# IoTa_1_0.net
KiCad netlist of a schematic drawn in Altium Designer
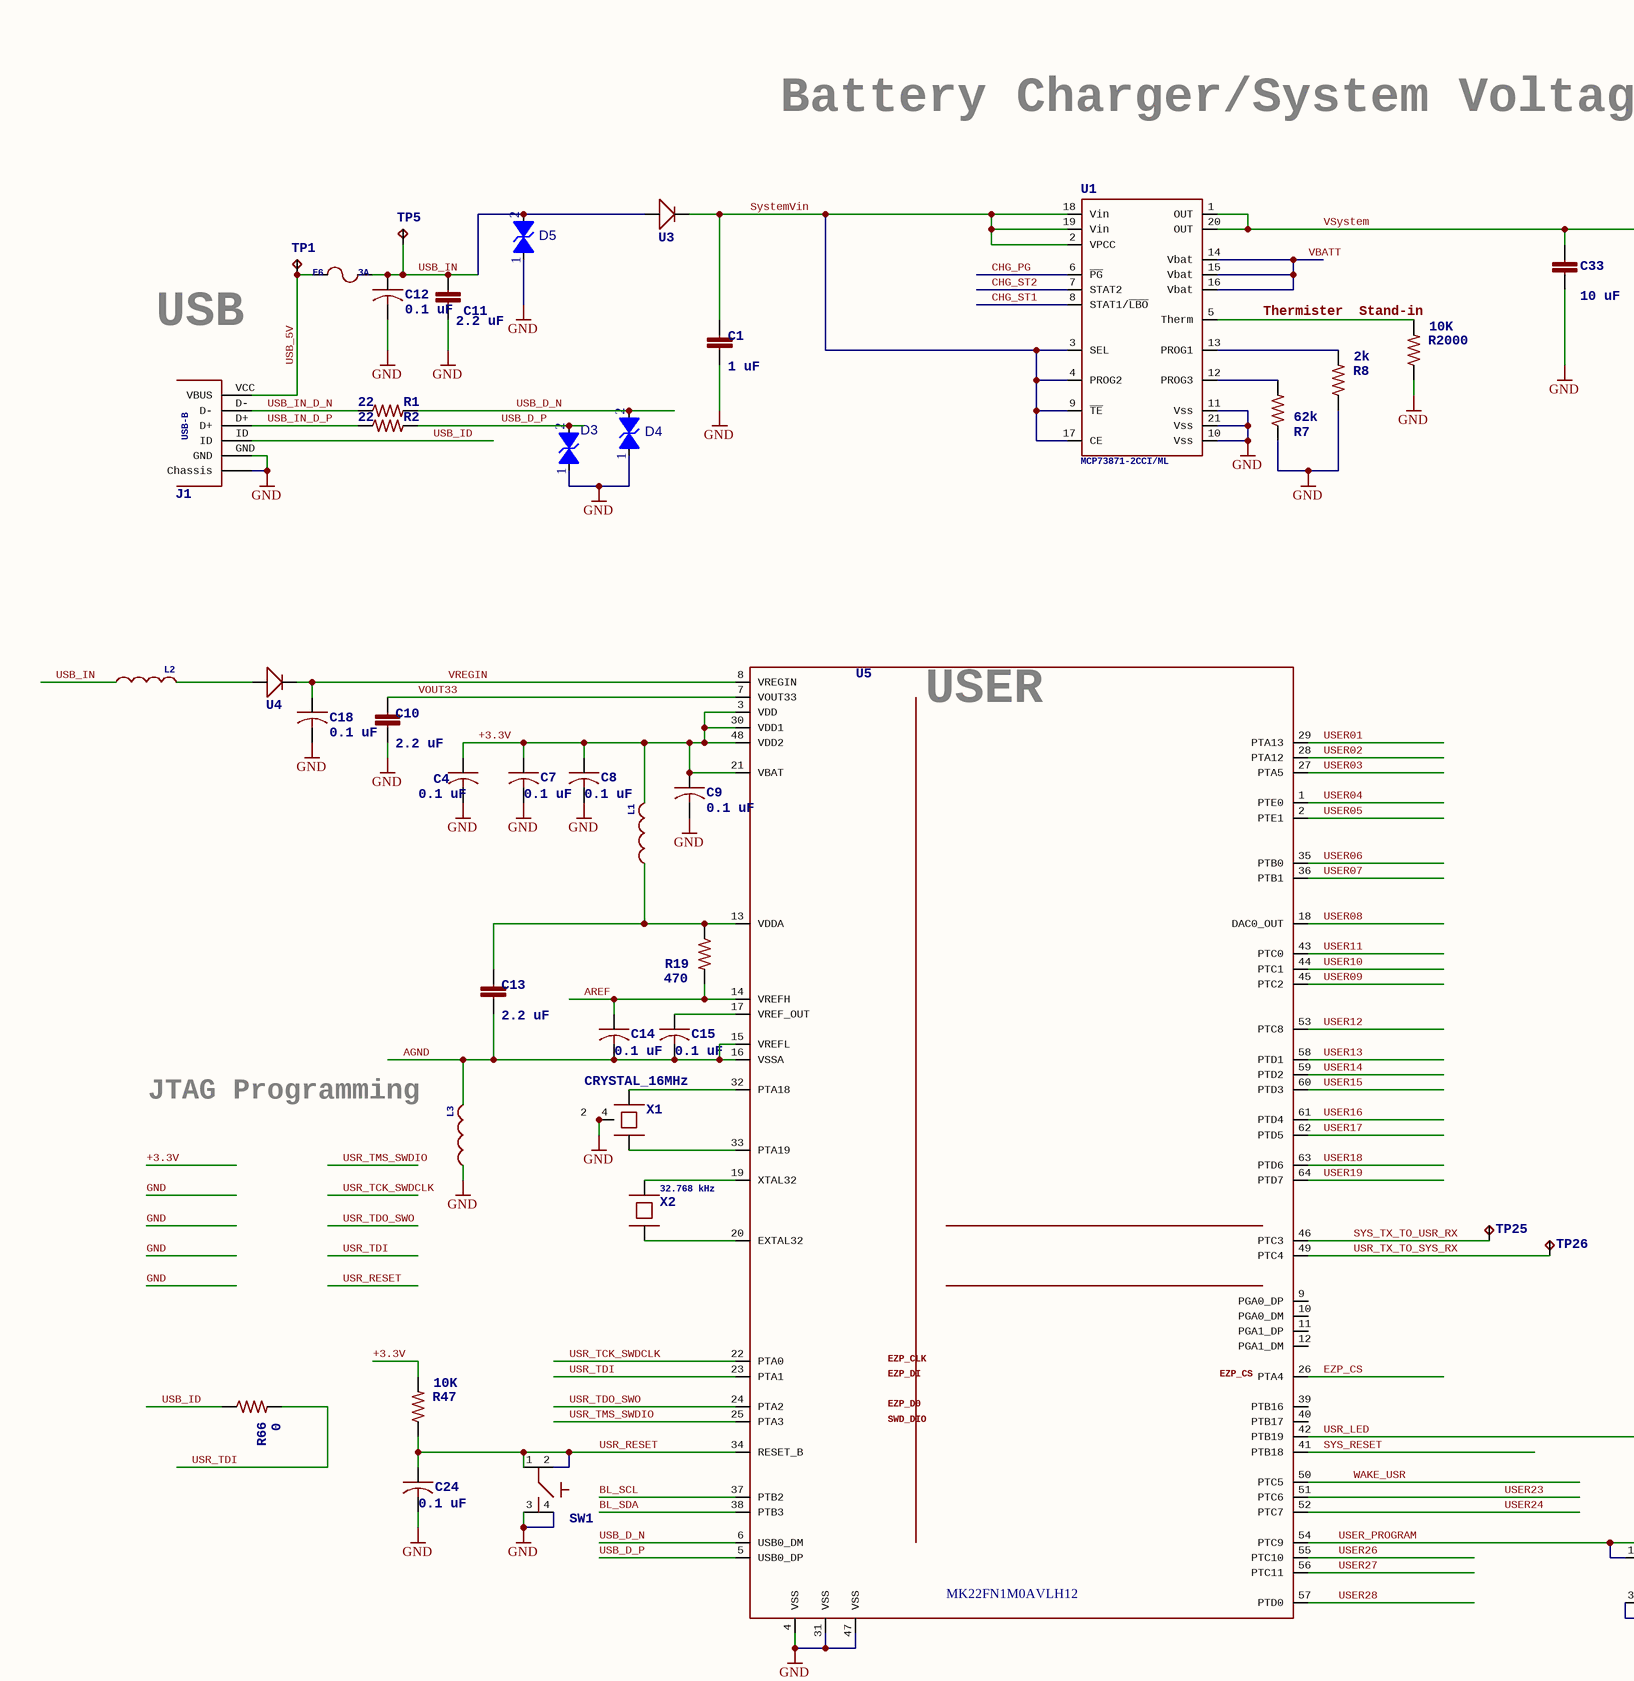
[diagram p0: IoTa_1_0.SchDoc, top left]
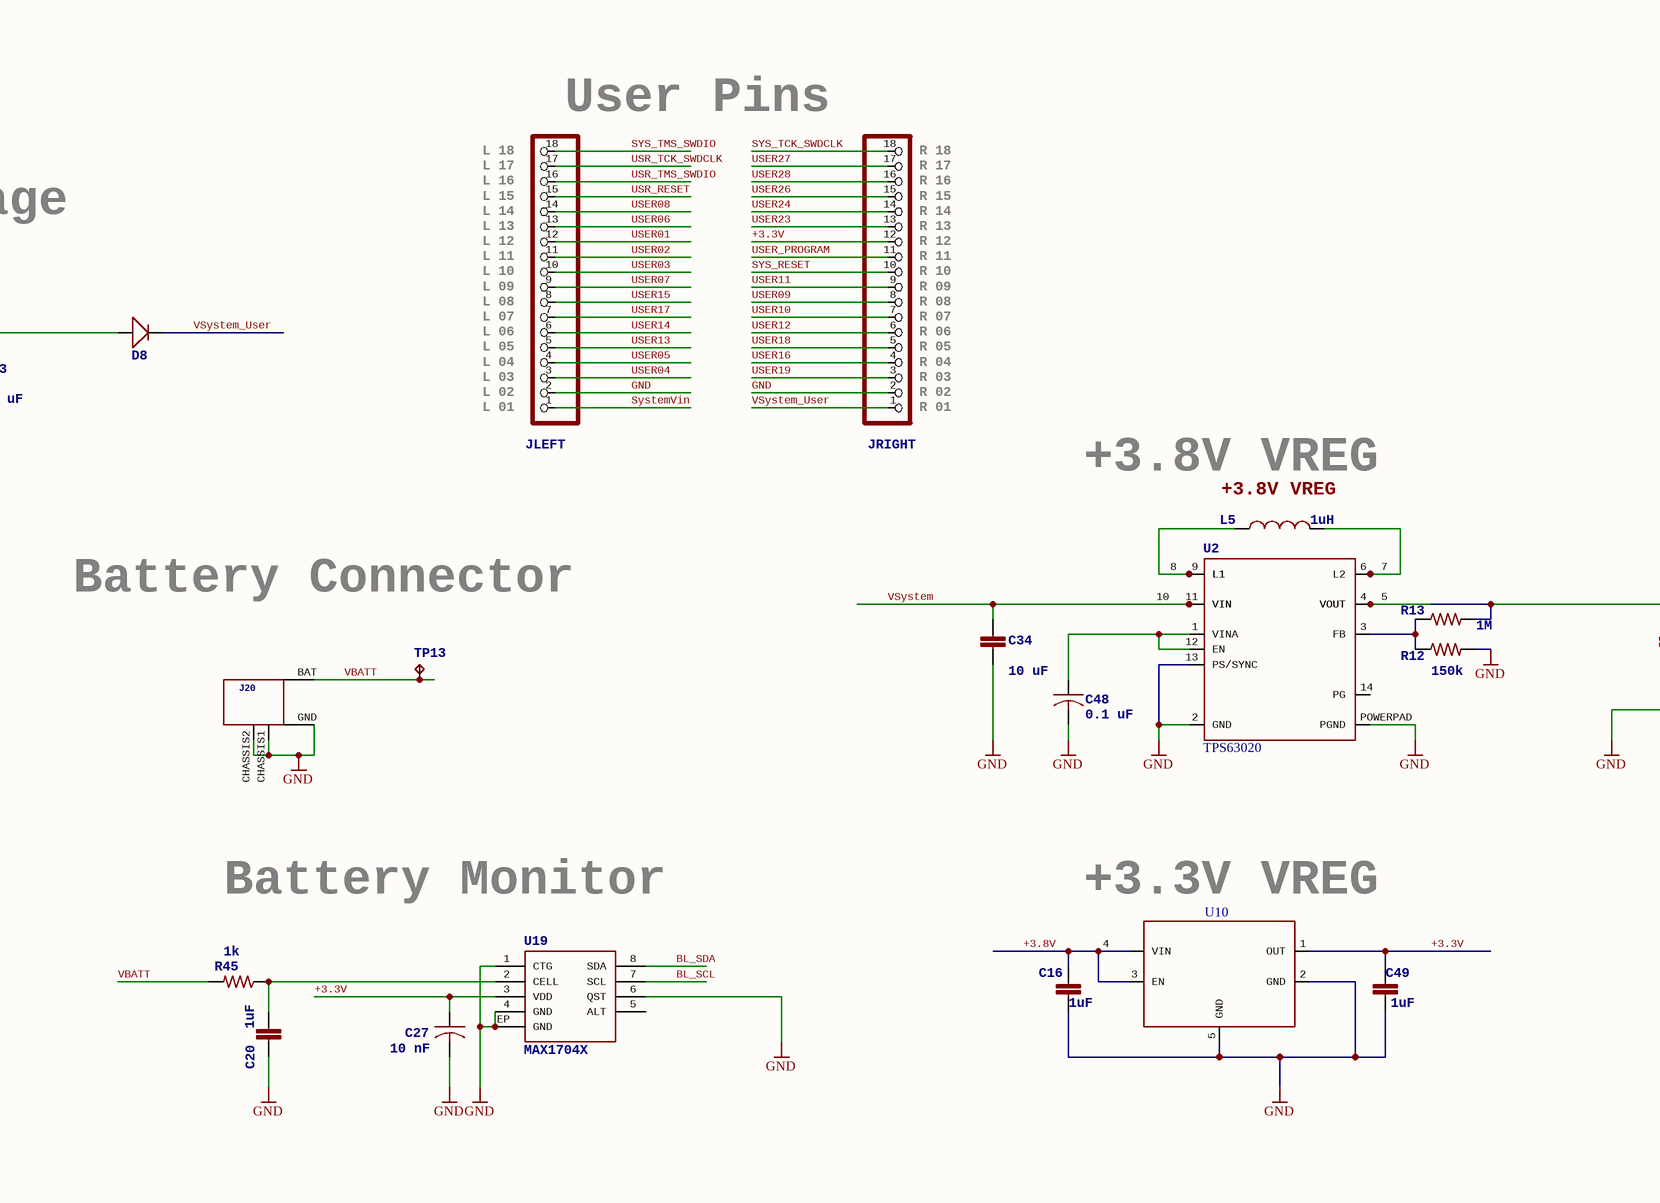
[diagram p1: IoTa_1_0.SchDoc, top middle]
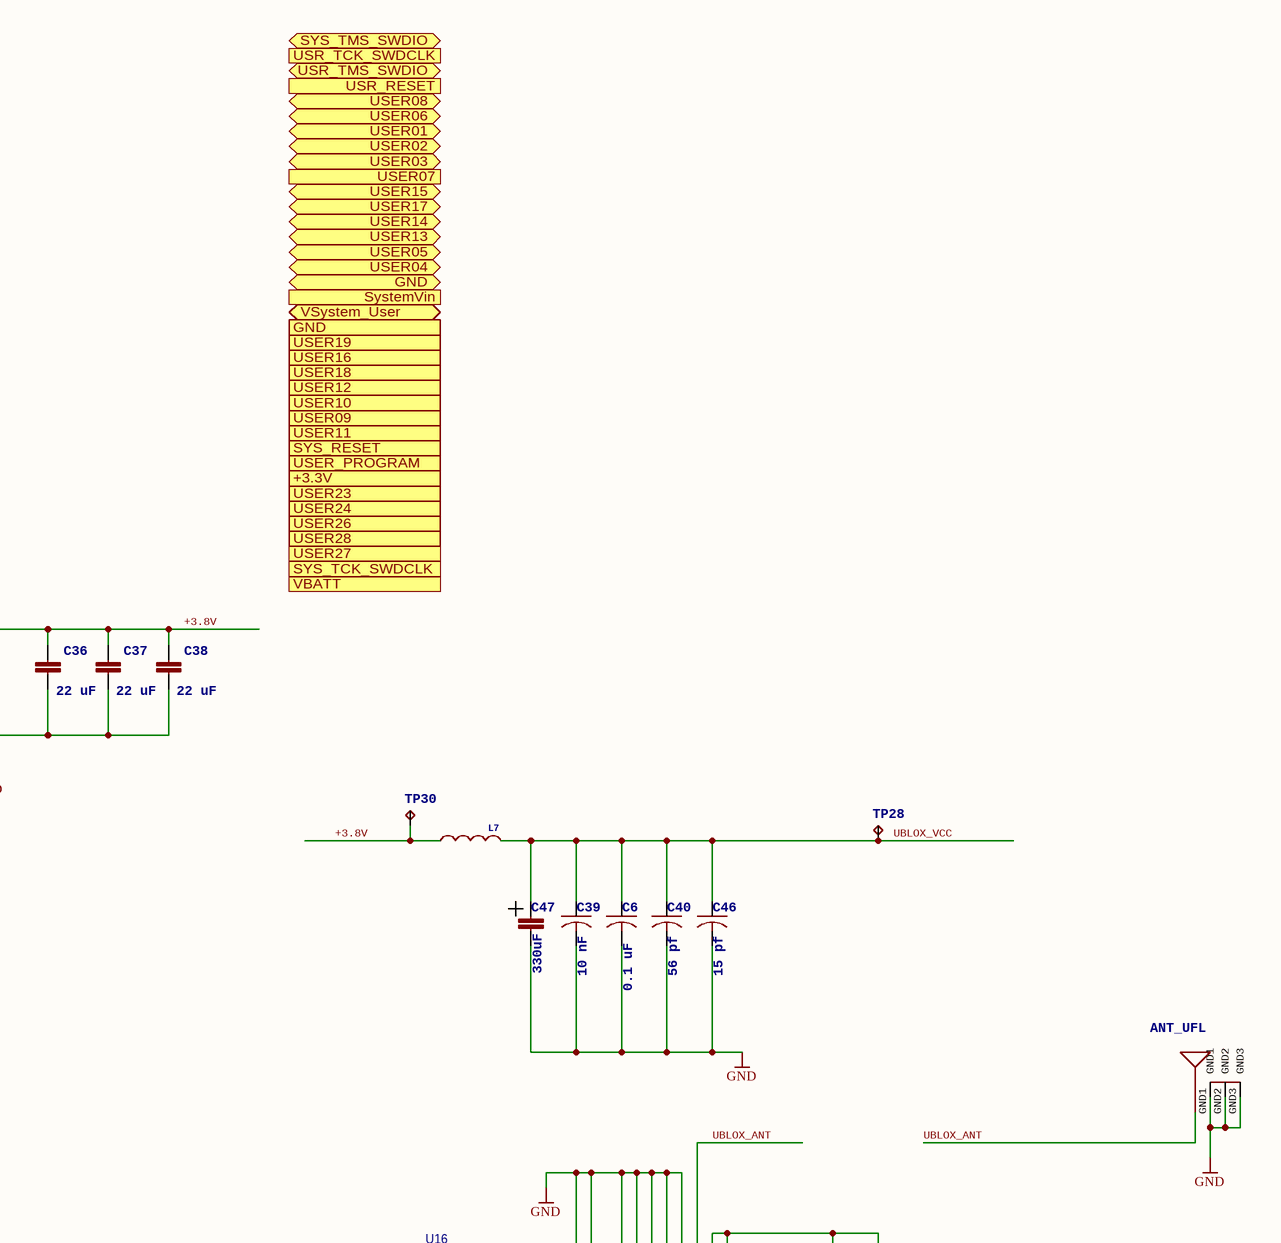
[diagram p2: IoTa_1_0.SchDoc, top right]
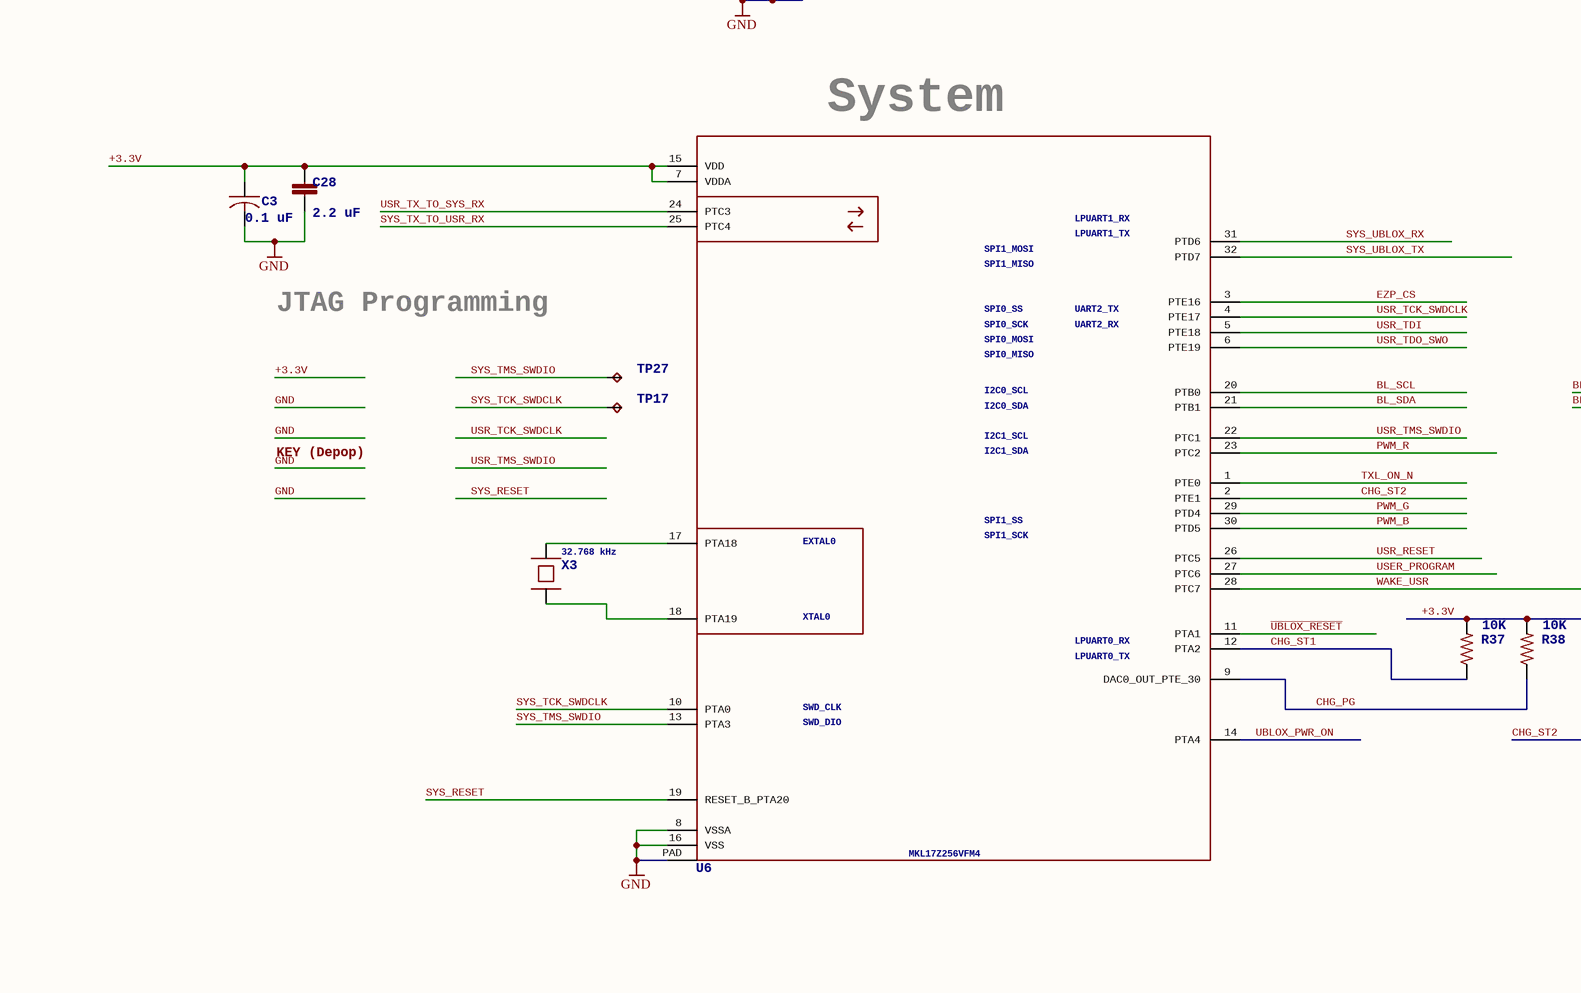
[diagram p3: IoTa_1_0.SchDoc, bottom left]
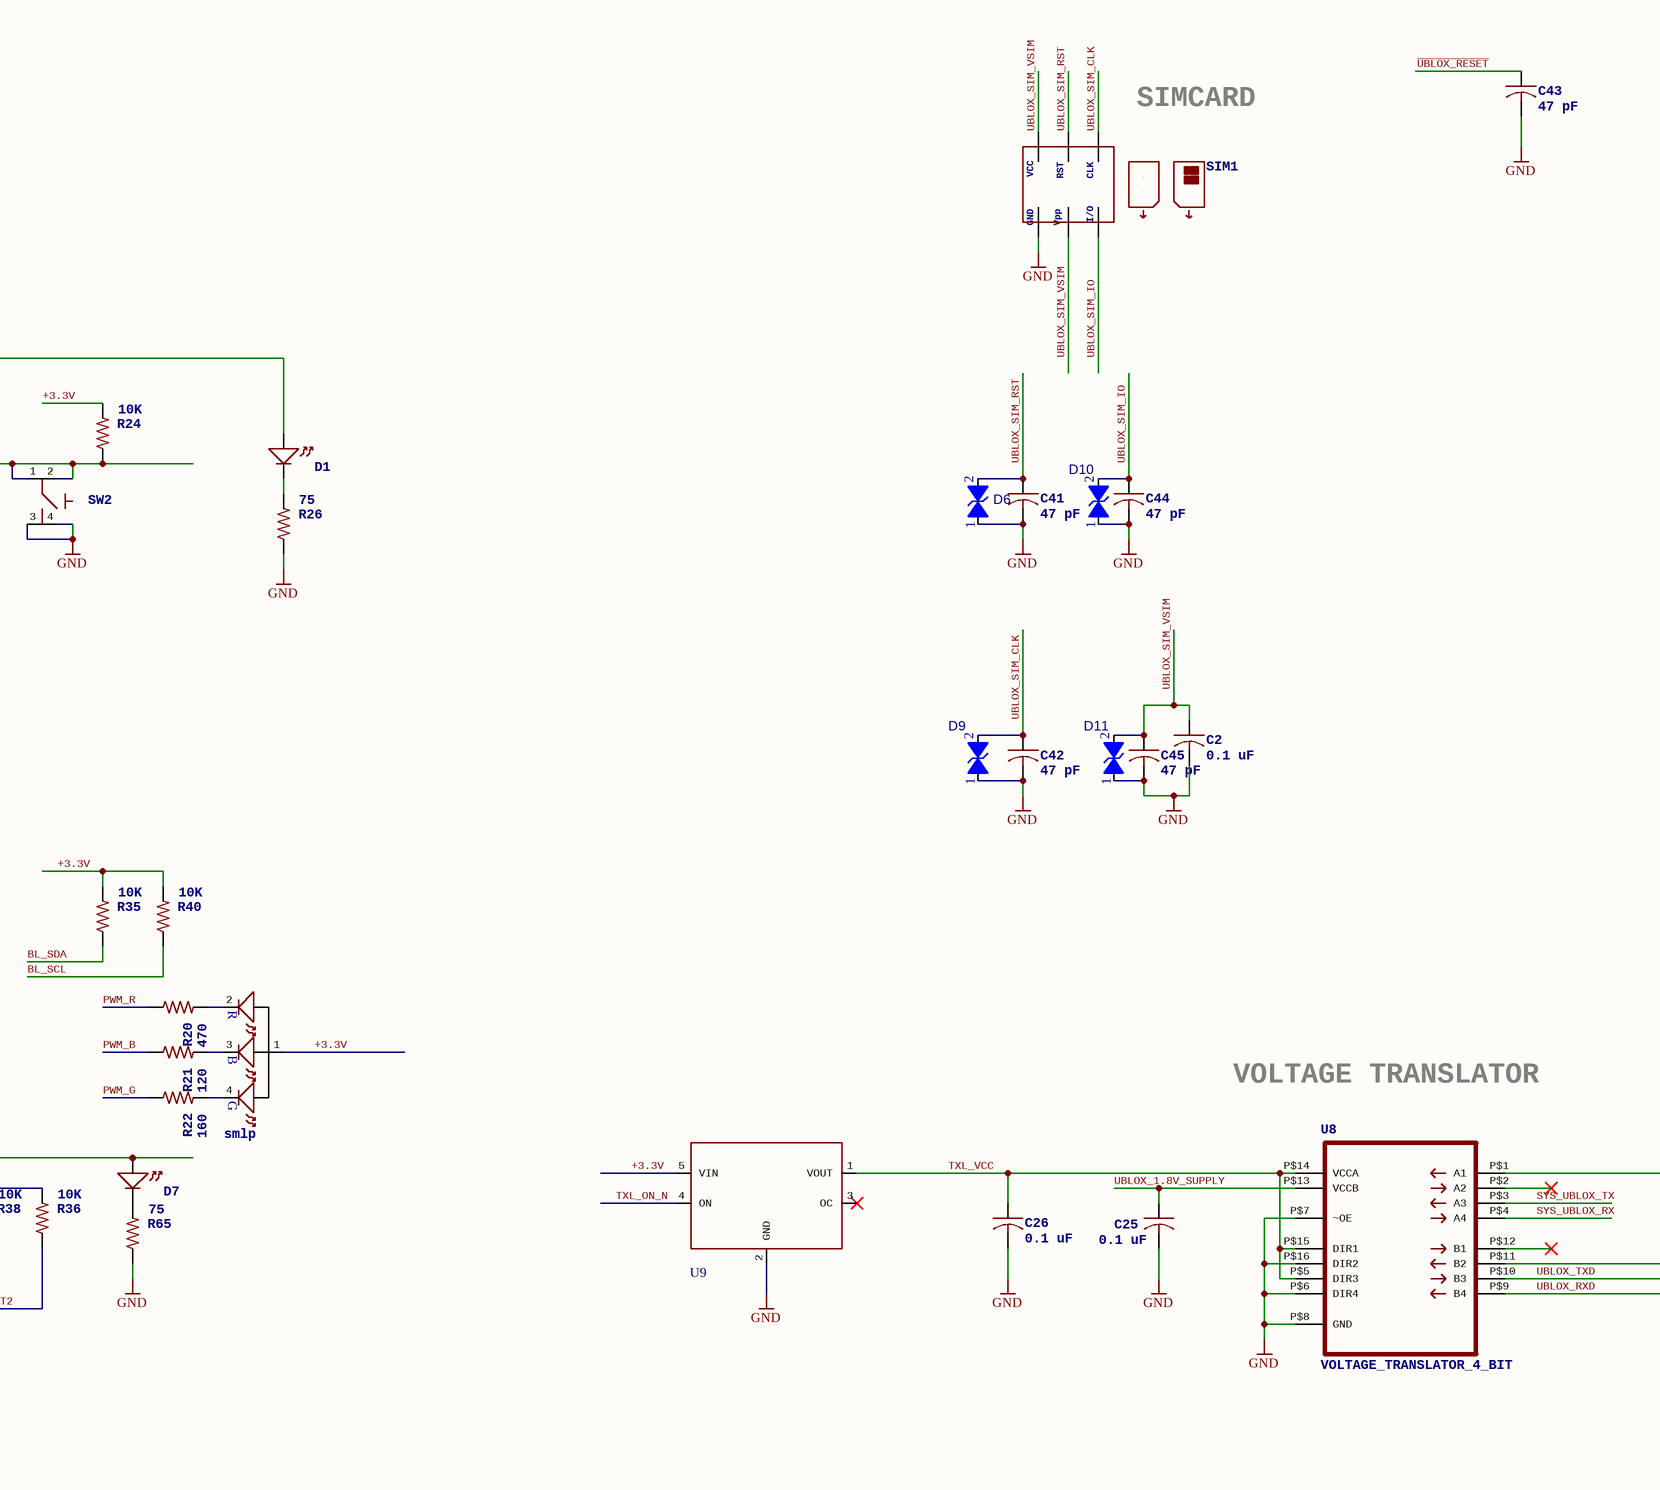
[diagram p4: IoTa_1_0.SchDoc, bottom middle]
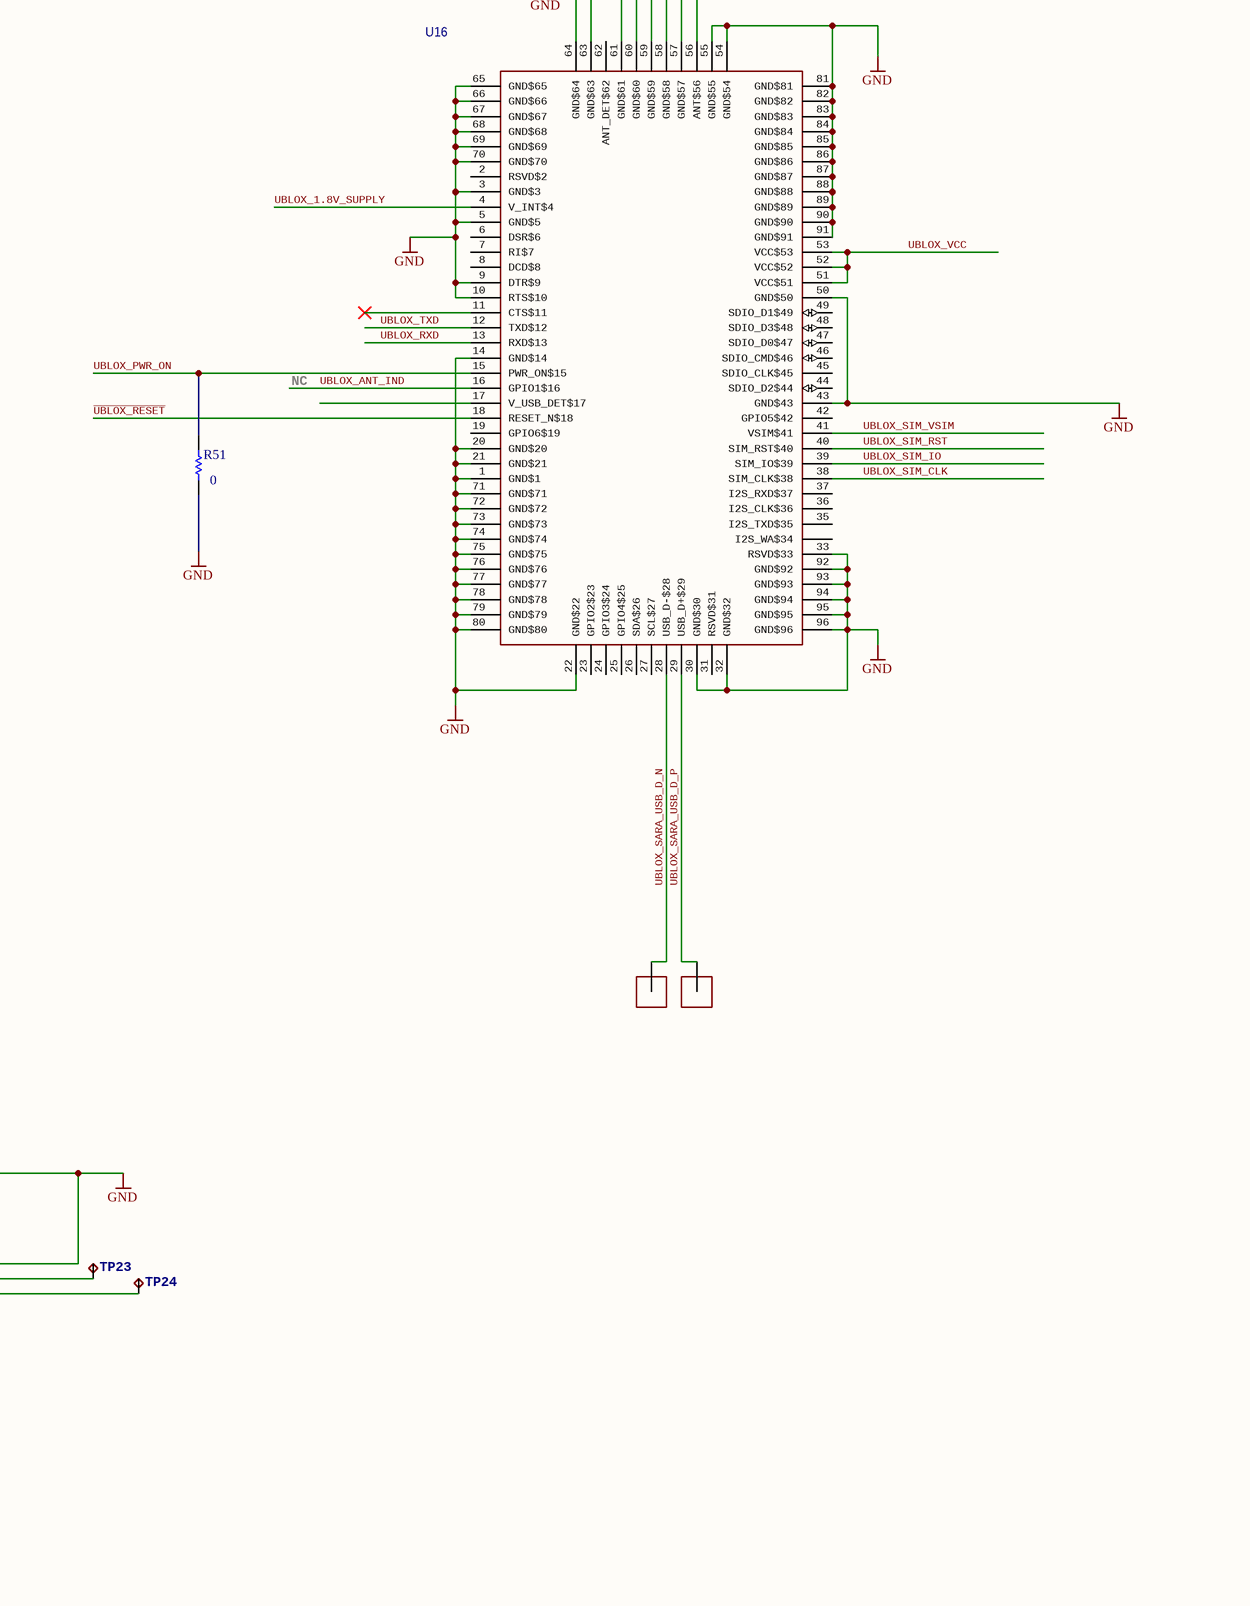
[diagram p5: IoTa_1_0.SchDoc, bottom right]

(export (version "E")
  (design (tool "Eeschema 10.0.6"))
  (components
    (comp (ref "ANT_UFL")
      (value "ANT-A-1JB")
      (footprint "UFL")
      (description "Amphenol")
      (fields (field (name "MPN") "A-1JB"))
      (libsource (lib "KON-SU260") (part "ANT-A-1JB"))
    )
    (comp (ref "C1")
      (value "1 uF")
      (footprint "KON-SU260:CAP0603")
      (description "Capacitor, 1 uF, 0603")
      (fields (field (name "MPN") "GRM188R71C105KA12D") (field (name "MFG") "MURATA"))
      (libsource (lib "KON-SU260") (part "CAP1uF_0603"))
    )
    (comp (ref "C2")
      (value "0.1 uF")
      (footprint "KON-SU260:CAP0402")
      (description "CAPACITOR, 0.1 uF, 0402")
      (fields (field (name "MFG") "MURATA") (field (name "MPN") "GRM155R61C104KA88D"))
      (libsource (lib "KON-SU260") (part "CAP0.1uF_0402"))
    )
    (comp (ref "C3")
      (value "0.1 uF")
      (footprint "KON-SU260:CAP0402")
      (description "CAPACITOR, 0.1 uF, 0402")
      (fields (field (name "MFG") "MURATA") (field (name "MPN") "GRM155R61C104KA88D"))
      (libsource (lib "KON-SU260") (part "CAP0.1uF_0402"))
    )
    (comp (ref "C4")
      (value "0.1 uF")
      (footprint "KON-SU260:CAP0402")
      (description "CAPACITOR, 0.1 uF, 0402")
      (fields (field (name "MFG") "MURATA") (field (name "MPN") "GRM155R61C104KA88D"))
      (libsource (lib "KON-SU260") (part "CAP0.1uF_0402"))
    )
    (comp (ref "C6")
      (value "0.1 uF")
      (footprint "KON-SU260:CAP0402")
      (description "CAPACITOR, 0.1 uF, 0402")
      (fields (field (name "MFG") "MURATA") (field (name "MPN") "GRM155R61C104KA88D"))
      (libsource (lib "KON-SU260") (part "CAP0.1uF_0402"))
    )
    (comp (ref "C7")
      (value "0.1 uF")
      (footprint "KON-SU260:CAP0402")
      (description "CAPACITOR, 0.1 uF, 0402")
      (fields (field (name "MFG") "MURATA") (field (name "MPN") "GRM155R61C104KA88D"))
      (libsource (lib "KON-SU260") (part "CAP0.1uF_0402"))
    )
    (comp (ref "C8")
      (value "0.1 uF")
      (footprint "KON-SU260:CAP0402")
      (description "CAPACITOR, 0.1 uF, 0402")
      (fields (field (name "MFG") "MURATA") (field (name "MPN") "GRM155R61C104KA88D"))
      (libsource (lib "KON-SU260") (part "CAP0.1uF_0402"))
    )
    (comp (ref "C9")
      (value "0.1 uF")
      (footprint "KON-SU260:CAP0402")
      (description "CAPACITOR, 0.1 uF, 0402")
      (fields (field (name "MFG") "MURATA") (field (name "MPN") "GRM155R61C104KA88D"))
      (libsource (lib "KON-SU260") (part "CAP0.1uF_0402"))
    )
    (comp (ref "C10")
      (value "2.2 uF")
      (footprint "KON-SU260:CAP0603")
      (description "Capacitor, 2.2 uF, 0603")
      (fields (field (name "MPN") "CL10A225MQ8NNNC") (field (name "MFG") "SAMSUNG"))
      (libsource (lib "KON-SU260") (part "CAP2.2uF_0603"))
    )
    (comp (ref "C11")
      (value "2.2 uF")
      (footprint "KON-SU260:CAP0603")
      (description "Capacitor, 2.2 uF, 0603")
      (fields (field (name "MPN") "CL10A225MQ8NNNC") (field (name "MFG") "SAMSUNG"))
      (libsource (lib "KON-SU260") (part "CAP2.2uF_0603"))
    )
    (comp (ref "C12")
      (value "0.1 uF")
      (footprint "KON-SU260:CAP0402")
      (description "CAPACITOR, 0.1 uF, 0402")
      (fields (field (name "MFG") "MURATA") (field (name "MPN") "GRM155R61C104KA88D"))
      (libsource (lib "KON-SU260") (part "CAP0.1uF_0402"))
    )
    (comp (ref "C13")
      (value "2.2 uF")
      (footprint "KON-SU260:CAP0603")
      (description "Capacitor, 2.2 uF, 0603")
      (fields (field (name "MPN") "CL10A225MQ8NNNC") (field (name "MFG") "SAMSUNG"))
      (libsource (lib "KON-SU260") (part "CAP2.2uF_0603"))
    )
    (comp (ref "C14")
      (value "0.1 uF")
      (footprint "KON-SU260:CAP0402")
      (description "CAPACITOR, 0.1 uF, 0402")
      (fields (field (name "MFG") "MURATA") (field (name "MPN") "GRM155R61C104KA88D"))
      (libsource (lib "KON-SU260") (part "CAP0.1uF_0402"))
    )
    (comp (ref "C15")
      (value "0.1 uF")
      (footprint "KON-SU260:CAP0402")
      (description "CAPACITOR, 0.1 uF, 0402")
      (fields (field (name "MFG") "MURATA") (field (name "MPN") "GRM155R61C104KA88D"))
      (libsource (lib "KON-SU260") (part "CAP0.1uF_0402"))
    )
    (comp (ref "C16")
      (value "1uF")
      (footprint "KON-SU260:CAP0402")
      (description "CAPACITOR, 1uF, 0402")
      (fields (field (name "MPN") "04026D105KAT2A") (field (name "MFG") "AVX"))
      (libsource (lib "KON-SU260") (part "CAP1uF_0402"))
    )
    (comp (ref "C18")
      (value "0.1 uF")
      (footprint "KON-SU260:CAP0402")
      (description "CAPACITOR, 0.1 uF, 0402")
      (fields (field (name "MFG") "MURATA") (field (name "MPN") "GRM155R61C104KA88D"))
      (libsource (lib "KON-SU260") (part "CAP0.1uF_0402"))
    )
    (comp (ref "C20")
      (value "1uF")
      (footprint "KON-SU260:CAP0402")
      (description "CAPACITOR, 1uF, 0402")
      (fields (field (name "MPN") "04026D105KAT2A") (field (name "MFG") "AVX"))
      (libsource (lib "KON-SU260") (part "CAP1uF_0402"))
    )
    (comp (ref "C24")
      (value "0.1 uF")
      (footprint "KON-SU260:CAP0402")
      (description "CAPACITOR, 0.1 uF, 0402")
      (fields (field (name "MFG") "MURATA") (field (name "MPN") "GRM155R61C104KA88D"))
      (libsource (lib "KON-SU260") (part "CAP0.1uF_0402"))
    )
    (comp (ref "C25")
      (value "0.1 uF")
      (footprint "KON-SU260:CAP0402")
      (description "CAPACITOR, 0.1 uF, 0402")
      (fields (field (name "MFG") "MURATA") (field (name "MPN") "GRM155R61C104KA88D"))
      (libsource (lib "KON-SU260") (part "CAP0.1uF_0402"))
    )
    (comp (ref "C26")
      (value "0.1 uF")
      (footprint "KON-SU260:CAP0402")
      (description "CAPACITOR, 0.1 uF, 0402")
      (fields (field (name "MFG") "MURATA") (field (name "MPN") "GRM155R61C104KA88D"))
      (libsource (lib "KON-SU260") (part "CAP0.1uF_0402"))
    )
    (comp (ref "C27")
      (value "10 nF")
      (footprint "KON-SU260:CAP0402")
      (description "CAPACITOR, 10 nF, 0402")
      (fields (field (name "MFG") "MURATA") (field (name "MPN") "GRM155R71C103KA01D"))
      (libsource (lib "KON-SU260") (part "CAP10nF_0402"))
    )
    (comp (ref "C28")
      (value "2.2 uF")
      (footprint "KON-SU260:CAP0603")
      (description "Capacitor, 2.2 uF, 0603")
      (fields (field (name "MPN") "CL10A225MQ8NNNC") (field (name "MFG") "SAMSUNG"))
      (libsource (lib "KON-SU260") (part "CAP2.2uF_0603"))
    )
    (comp (ref "C33")
      (value "10 uF")
      (footprint "KON-SU260:CAP0603")
      (description "Capacitor, 10 uF, 0603")
      (fields (field (name "MPN") "GRM188R60J106ME84D") (field (name "MFG") "Murata"))
      (libsource (lib "KON-SU260") (part "CAP10uF_0603"))
    )
    (comp (ref "C34")
      (value "10 uF")
      (footprint "KON-SU260:CAP0603")
      (description "Capacitor, 10 uF, 0603")
      (fields (field (name "MPN") "GRM188R60J106ME84D") (field (name "MFG") "Murata"))
      (libsource (lib "KON-SU260") (part "CAP10uF_0603"))
    )
    (comp (ref "C36")
      (value "22 uF")
      (footprint "KON-SU260:CAP0603")
      (description "Capacitor, 22 uF, 0603")
      (fields (field (name "MPN") "GRM188R60J226MEA0D") (field (name "MFG") "MURATA"))
      (libsource (lib "KON-SU260") (part "CAP22uF_0603"))
    )
    (comp (ref "C37")
      (value "22 uF")
      (footprint "KON-SU260:CAP0603")
      (description "Capacitor, 22 uF, 0603")
      (fields (field (name "MPN") "GRM188R60J226MEA0D") (field (name "MFG") "MURATA"))
      (libsource (lib "KON-SU260") (part "CAP22uF_0603"))
    )
    (comp (ref "C38")
      (value "22 uF")
      (footprint "KON-SU260:CAP0603")
      (description "Capacitor, 22 uF, 0603")
      (fields (field (name "MPN") "GRM188R60J226MEA0D") (field (name "MFG") "MURATA"))
      (libsource (lib "KON-SU260") (part "CAP22uF_0603"))
    )
    (comp (ref "C39")
      (value "10 nF")
      (footprint "KON-SU260:CAP0402")
      (description "CAPACITOR, 10 nF, 0402")
      (fields (field (name "MFG") "MURATA") (field (name "MPN") "GRM155R71C103KA01D"))
      (libsource (lib "KON-SU260") (part "CAP10nF_0402"))
    )
    (comp (ref "C40")
      (value "56 pf")
      (footprint "KON-SU260:CAP0402")
      (description "CAPACITOR, 56 pF, 0402")
      (fields (field (name "MFG") "KEMET") (field (name "MPN") "C0402C560J5GACTU"))
      (libsource (lib "KON-SU260") (part "CAP56pF_0402"))
    )
    (comp (ref "C41")
      (value "47 pF")
      (footprint "KON-SU260:CAP0402")
      (description "CAPACITOR, 47 pF, 0402")
      (fields (field (name "MFG") "AVX") (field (name "MPN") "04025A470JAT2A"))
      (libsource (lib "KON-SU260") (part "CAP47pf_0402"))
    )
    (comp (ref "C42")
      (value "47 pF")
      (footprint "KON-SU260:CAP0402")
      (description "CAPACITOR, 47 pF, 0402")
      (fields (field (name "MFG") "AVX") (field (name "MPN") "04025A470JAT2A"))
      (libsource (lib "KON-SU260") (part "CAP47pf_0402"))
    )
    (comp (ref "C43")
      (value "47 pF")
      (footprint "KON-SU260:CAP0402")
      (description "CAPACITOR, 47 pF, 0402")
      (fields (field (name "MFG") "AVX") (field (name "MPN") "04025A470JAT2A"))
      (libsource (lib "KON-SU260") (part "CAP47pf_0402"))
    )
    (comp (ref "C44")
      (value "47 pF")
      (footprint "KON-SU260:CAP0402")
      (description "CAPACITOR, 47 pF, 0402")
      (fields (field (name "MFG") "AVX") (field (name "MPN") "04025A470JAT2A"))
      (libsource (lib "KON-SU260") (part "CAP47pf_0402"))
    )
    (comp (ref "C45")
      (value "47 pF")
      (footprint "KON-SU260:CAP0402")
      (description "CAPACITOR, 47 pF, 0402")
      (fields (field (name "MFG") "AVX") (field (name "MPN") "04025A470JAT2A"))
      (libsource (lib "KON-SU260") (part "CAP47pf_0402"))
    )
    (comp (ref "C46")
      (value "15 pf")
      (footprint "KON-SU260:CAP0402")
      (description "CAPACITOR, 15 pF, 0402")
      (fields (field (name "MFG") "AVX/ELCO") (field (name "MPN") "04025A150JAT2A"))
      (libsource (lib "KON-SU260") (part "CAP15pF_0402"))
    )
    (comp (ref "C47")
      (value "330uF")
      (footprint "KON-SU260:CAP1210POL")
      (description "Capacitor, 330 uF, 1210, Polarized Tantalum")
      (fields (field (name "MPN") "F950J337MBAAQ2") (field (name "MFG") "AVX"))
      (libsource (lib "KON-SU260") (part "CAP330uF_1210P"))
    )
    (comp (ref "C48")
      (value "0.1 uF")
      (footprint "KON-SU260:CAP0402")
      (description "CAPACITOR, 0.1 uF, 0402")
      (fields (field (name "MFG") "MURATA") (field (name "MPN") "GRM155R61C104KA88D"))
      (libsource (lib "KON-SU260") (part "CAP0.1uF_0402"))
    )
    (comp (ref "C49")
      (value "1uF")
      (footprint "KON-SU260:CAP0402")
      (description "CAPACITOR, 1uF, 0402")
      (fields (field (name "MPN") "04026D105KAT2A") (field (name "MFG") "AVX"))
      (libsource (lib "KON-SU260") (part "CAP1uF_0402"))
    )
    (comp (ref "D1")
      (value "LED_0402_VLMW")
      (footprint "LED_0402_VISHAY_VLMW")
      (description "LED, Vishay White 0402")
      (fields (field (name "MFG") "VISHAY") (field (name "MPN") "VLMW1500-GS08"))
      (libsource (lib "KON-SU260") (part "LED_0402_VLMW"))
    )
    (comp (ref "D3")
      (value "~")
      (footprint "PESD_0402")
      (description "DIODE,ZENER VOLTAGE SUPPRESSOR,+/-14V")
      (fields (field (name "MFG") "Littlefuse") (field (name "MPN") "PESD0402-140"))
      (libsource (lib "KON-SU260") (part "PESD_14V"))
    )
    (comp (ref "D4")
      (value "~")
      (footprint "PESD_0402")
      (description "DIODE,ZENER VOLTAGE SUPPRESSOR,+/-14V")
      (fields (field (name "MFG") "Littlefuse") (field (name "MPN") "PESD0402-140"))
      (libsource (lib "KON-SU260") (part "PESD_14V"))
    )
    (comp (ref "D5")
      (value "~")
      (footprint "PESD_0402")
      (description "DIODE,ZENER VOLTAGE SUPPRESSOR,+/-14V")
      (fields (field (name "MFG") "Littlefuse") (field (name "MPN") "PESD0402-140"))
      (libsource (lib "KON-SU260") (part "PESD_14V"))
    )
    (comp (ref "D6")
      (value "~")
      (footprint "PESD_0402")
      (description "DIODE,ZENER VOLTAGE SUPPRESSOR,+/-14V")
      (fields (field (name "MFG") "Littlefuse") (field (name "MPN") "PESD0402-140"))
      (libsource (lib "KON-SU260") (part "PESD_14V"))
    )
    (comp (ref "D7")
      (value "LED_0402_VLMW")
      (footprint "LED_0402_VISHAY_VLMW")
      (description "LED, Vishay White 0402")
      (fields (field (name "MFG") "VISHAY") (field (name "MPN") "VLMW1500-GS08"))
      (libsource (lib "KON-SU260") (part "LED_0402_VLMW"))
    )
    (comp (ref "D8")
      (value "CDBQR0230L")
      (footprint "DIODE_0402")
      (description "Schottky Barrier Diode, 200 mA, 30 V, 0402 package")
      (fields (field (name "MFG") "Comchip"))
      (libsource (lib "KON-SU260") (part "DIODE_0402_200mA"))
    )
    (comp (ref "D9")
      (value "~")
      (footprint "PESD_0402")
      (description "DIODE,ZENER VOLTAGE SUPPRESSOR,+/-14V")
      (fields (field (name "MFG") "Littlefuse") (field (name "MPN") "PESD0402-140"))
      (libsource (lib "KON-SU260") (part "PESD_14V"))
    )
    (comp (ref "D10")
      (value "~")
      (footprint "PESD_0402")
      (description "DIODE,ZENER VOLTAGE SUPPRESSOR,+/-14V")
      (fields (field (name "MFG") "Littlefuse") (field (name "MPN") "PESD0402-140"))
      (libsource (lib "KON-SU260") (part "PESD_14V"))
    )
    (comp (ref "D11")
      (value "~")
      (footprint "PESD_0402")
      (description "DIODE,ZENER VOLTAGE SUPPRESSOR,+/-14V")
      (fields (field (name "MFG") "Littlefuse") (field (name "MPN") "PESD0402-140"))
      (libsource (lib "KON-SU260") (part "PESD_14V"))
    )
    (comp (ref "F6")
      (value "3A")
      (footprint "KON-SU260:RES0603")
      (description "Fuse, 3A, 0603")
      (fields (field (name "MFG") "Bourns") (field (name "MPN") "SF-0603S300-2"))
      (libsource (lib "KON-SU260") (part "FUSE_0603"))
    )
    (comp (ref "J1")
      (value "Micro USB B FCI 10118193")
      (footprint "USB_MICRO_FCI_10118193")
      (description "Connector, Micro USB B, FCI")
      (fields
        (field (name "MFG") "Amphenol FCI")
        (field (name "MPN") "10118193-0001LF")
        (field (name "USB-B") "USB-B")
      )
      (libsource (lib "KON-SU260") (part "USB_MICRO_B_FCI_10118193"))
    )
    (comp (ref "J20")
      (value "BAT_TERM_TOP_ENTRY")
      (footprint "JST-PH-2-Top")
      (description "Battery Connector JST-PH2 Top Entry")
      (fields (field (name "MPN") "B2B-PH-SM4-TB(LF)(SN)") (field (name "MFG") "JST"))
      (libsource (lib "KON-SU260") (part "BAT_TERM_TOP_ENTRY"))
    )
    (comp (ref "JLEFT")
      (value "22-28-4180")
      (footprint "KON-SU260:1X18")
      (description "Header, Male, 1x18, 0.1\"")
      (fields (field (name "MFG") "MOLEX"))
      (libsource (lib "KON-SU260") (part "PINHD-1X18"))
    )
    (comp (ref "JRIGHT")
      (value "22-28-4180")
      (footprint "KON-SU260:1X18")
      (description "Header, Male, 1x18, 0.1\"")
      (fields (field (name "MFG") "MOLEX"))
      (libsource (lib "KON-SU260") (part "PINHD-1X18"))
    )
    (comp (ref "L1")
      (value "FerriteBead_220ohm")
      (footprint "KON-SU260:RES0603")
      (description "FerriteBead, 220ohm")
      (fields (field (name "MPN") "BLM18AG121SN1D") (field (name "MFG") "Murata"))
      (libsource (lib "KON-SU260") (part "FerriteBead_220ohm"))
    )
    (comp (ref "L2")
      (value "FerriteBead_220ohm")
      (footprint "KON-SU260:RES0603")
      (description "FerriteBead, 220ohm")
      (fields (field (name "MPN") "BLM18AG121SN1D") (field (name "MFG") "Murata"))
      (libsource (lib "KON-SU260") (part "FerriteBead_220ohm"))
    )
    (comp (ref "L3")
      (value "FerriteBead_220ohm")
      (footprint "KON-SU260:RES0603")
      (description "FerriteBead, 220ohm")
      (fields (field (name "MPN") "BLM18AG121SN1D") (field (name "MFG") "Murata"))
      (libsource (lib "KON-SU260") (part "FerriteBead_220ohm"))
    )
    (comp (ref "L5")
      (value "1uH")
      (footprint "COILCRAFT_XFL4020")
      (description "Inductor, 1 uH, Coilcraft")
      (fields (field (name "MPN") "XFL4020-102MEC") (field (name "MFG") "Coilcraft"))
      (libsource (lib "KON-SU260") (part "INDUCTOR_1UH_XFL4020-102MEC"))
    )
    (comp (ref "L7")
      (value "FerriteBead_220ohm")
      (footprint "KON-SU260:RES0603")
      (description "FerriteBead, 220ohm")
      (fields (field (name "MPN") "BLM18AG121SN1D") (field (name "MFG") "Murata"))
      (libsource (lib "KON-SU260") (part "FerriteBead_220ohm"))
    )
    (comp (ref "R1")
      (value "22")
      (footprint "KON-SU260:RES0402")
      (description "Resistor, 22 ohm, 0402 case, 1%")
      (fields (field (name "MFG") "YAEGO") (field (name "MPN") "RC0402FR-0722RL"))
      (libsource (lib "KON-SU260") (part "RES22R_0402"))
    )
    (comp (ref "R2")
      (value "22")
      (footprint "KON-SU260:RES0402")
      (description "Resistor, 22 ohm, 0402 case, 1%")
      (fields (field (name "MFG") "YAEGO") (field (name "MPN") "RC0402FR-0722RL"))
      (libsource (lib "KON-SU260") (part "RES22R_0402"))
    )
    (comp (ref "R7")
      (value "62k")
      (footprint "KON-SU260:RES0402")
      (description "Resistor, 62K ohm, 0402 case")
      (fields (field (name "MFG") "YAEGO") (field (name "MPN") "RC0402FR-0762KL"))
      (libsource (lib "KON-SU260") (part "RES62K_0402_1"))
    )
    (comp (ref "R8")
      (value "2k")
      (footprint "KON-SU260:RES0402")
      (description "Resistor, 2K ohm, 0402 case")
      (fields (field (name "MFG") "YAEGO") (field (name "MPN") "RC0402FR-072KL"))
      (libsource (lib "KON-SU260") (part "RES2K_0402"))
    )
    (comp (ref "R12")
      (value "150k")
      (footprint "KON-SU260:RES0402")
      (description "Res, 150k ohm, 0402 case, 1%")
      (fields (field (name "MFG") "YAEGO") (field (name "MPN") "RC0402FR-07150KL"))
      (libsource (lib "KON-SU260") (part "RES150K_0402"))
    )
    (comp (ref "R13")
      (value "1M")
      (footprint "KON-SU260:RES0402")
      (description "Resistor, 1M ohm, 0402 case, 1%")
      (fields (field (name "MFG") "YAEGO") (field (name "MPN") "RC0402FR-071ML"))
      (libsource (lib "KON-SU260") (part "RES1M_0402"))
    )
    (comp (ref "R19")
      (value "470")
      (footprint "KON-SU260:RES0402")
      (description "Resistor, 470 ohm, 0402 case, 1%")
      (fields (field (name "MFG") "PANASONIC") (field (name "MPN") "ERJ-2GEJ471X"))
      (libsource (lib "KON-SU260") (part "RES470R_0402"))
    )
    (comp (ref "R20")
      (value "470")
      (footprint "KON-SU260:RES0402")
      (description "Resistor, 470 ohm, 0402 case, 1%")
      (fields (field (name "MFG") "PANASONIC") (field (name "MPN") "ERJ-2GEJ471X"))
      (libsource (lib "KON-SU260") (part "RES470R_0402"))
    )
    (comp (ref "R21")
      (value "120")
      (footprint "KON-SU260:RES0402")
      (description "Resistor, 120 ohm, 0402 case, 1%")
      (fields (field (name "MFG") "PANASONIC") (field (name "MPN") "ERJ-2GEJ121X"))
      (libsource (lib "KON-SU260") (part "RES120R_0402"))
    )
    (comp (ref "R22")
      (value "160")
      (footprint "KON-SU260:RES0402")
      (description "Resistor, 160 ohm, 0402 case, 1%")
      (fields (field (name "MFG") "PANASONIC") (field (name "MPN") "ERJ-2GEJ161X"))
      (libsource (lib "KON-SU260") (part "RES160R_0402"))
    )
    (comp (ref "R24")
      (value "10K")
      (footprint "KON-SU260:RES0402")
      (description "Resistor, 10k ohm, 0402")
      (fields (field (name "MFG") "YAEGO") (field (name "MPN") "RC0402JR-0710KL"))
      (libsource (lib "KON-SU260") (part "RES10K_0402"))
    )
    (comp (ref "R26")
      (value "75")
      (footprint "KON-SU260:RES0402")
      (description "Resistor, 75 ohm, 0402, 1%")
      (fields (field (name "MFG") "YAEGO") (field (name "MPN") "RC0402FR-0775RL"))
      (libsource (lib "KON-SU260") (part "RES75R_0402"))
    )
    (comp (ref "R35")
      (value "10K")
      (footprint "KON-SU260:RES0402")
      (description "Resistor, 10k ohm, 0402")
      (fields (field (name "MFG") "YAEGO") (field (name "MPN") "RC0402JR-0710KL"))
      (libsource (lib "KON-SU260") (part "RES10K_0402"))
    )
    (comp (ref "R36")
      (value "10K")
      (footprint "KON-SU260:RES0402")
      (description "Resistor, 10k ohm, 0402")
      (fields (field (name "MFG") "YAEGO") (field (name "MPN") "RC0402JR-0710KL"))
      (libsource (lib "KON-SU260") (part "RES10K_0402"))
    )
    (comp (ref "R37")
      (value "10K")
      (footprint "KON-SU260:RES0402")
      (description "Resistor, 10k ohm, 0402")
      (fields (field (name "MFG") "YAEGO") (field (name "MPN") "RC0402JR-0710KL"))
      (libsource (lib "KON-SU260") (part "RES10K_0402"))
    )
    (comp (ref "R38")
      (value "10K")
      (footprint "KON-SU260:RES0402")
      (description "Resistor, 10k ohm, 0402")
      (fields (field (name "MFG") "YAEGO") (field (name "MPN") "RC0402JR-0710KL"))
      (libsource (lib "KON-SU260") (part "RES10K_0402"))
    )
    (comp (ref "R40")
      (value "10K")
      (footprint "KON-SU260:RES0402")
      (description "Resistor, 10k ohm, 0402")
      (fields (field (name "MFG") "YAEGO") (field (name "MPN") "RC0402JR-0710KL"))
      (libsource (lib "KON-SU260") (part "RES10K_0402"))
    )
    (comp (ref "R45")
      (value "1k")
      (footprint "KON-SU260:RES0402")
      (description "Resistor, 1k, 0402 case, 1%")
      (fields (field (name "MFG") "YAEGO") (field (name "MPN") "RC0402JR-071KL"))
      (libsource (lib "KON-SU260") (part "RES1K_0402"))
    )
    (comp (ref "R47")
      (value "10K")
      (footprint "KON-SU260:RES0402")
      (description "Resistor, 10k ohm, 0402")
      (fields (field (name "MFG") "YAEGO") (field (name "MPN") "RC0402JR-0710KL"))
      (libsource (lib "KON-SU260") (part "RES10K_0402"))
    )
    (comp (ref "R51")
      (value "0")
      (footprint "RESC2013X50X30LL20T20")
      (fields (field (name "MANUFACTURER") "Vishay Dale") (field (name "PART NUMBER") "CRCW08050000Z0EA"))
      (libsource (lib "Altium Content Vault") (part "RES"))
    )
    (comp (ref "R65")
      (value "75")
      (footprint "KON-SU260:RES0402")
      (description "Resistor, 75 ohm, 0402, 1%")
      (fields (field (name "MFG") "YAEGO") (field (name "MPN") "RC0402FR-0775RL"))
      (libsource (lib "KON-SU260") (part "RES75R_0402"))
    )
    (comp (ref "R66")
      (value "0")
      (footprint "KON-SU260:RES0402")
      (description "Resistor, 0 ohm, 0402")
      (fields (field (name "MFG") "PANASONIC") (field (name "MPN") "ERJ-2GE0R00X"))
      (libsource (lib "KON-SU260") (part "RES0R_0402"))
    )
    (comp (ref "R2000")
      (value "10K")
      (footprint "KON-SU260:RES0402")
      (description "Resistor, 10k ohm, 0402")
      (fields (field (name "MFG") "YAEGO") (field (name "MPN") "RC0402JR-0710KL"))
      (libsource (lib "KON-SU260") (part "RES10K_0402"))
    )
    (comp (ref "SIM1")
      (value "SIM_CARD_NANO")
      (footprint "SIM_CARD_NANO")
      (description "Connector, SIM Card,Nano")
      (fields
        (field (name "MFG") "GLOBAL CONNECTOR TECHNOLOGY")
        (field (name "MPN") "SIM8050-6-0-14-01-A")
        (field (name "VCC") "VCC")
        (field (name "RST") "RST")
        (field (name "CLK") "CLK")
        (field (name "I/O") "I/O")
        (field (name "VPP") "Vpp")
        (field (name "GND") "GND")
      )
      (libsource (lib "KON-SU260") (part "SIM_CARD_NANO"))
    )
    (comp (ref "smlp")
      (value "LED_RGB_1mm_sq")
      (footprint "PT-IoTa_1_0:LED-RGB-1X1")
      (description "LED, Tri-color, RGB, 1mm sq")
      (fields (field (name "MFG") "Rohm") (field (name "MPN") "SMLP34RGB1W3"))
      (libsource (lib "KON-SU260") (part "LED_RGB_1mm_sq"))
    )
    (comp (ref "SW1")
      (value "SWITCH_PTS810")
      (footprint "SWITCH_PTS810")
      (description "Switch, C&K, PTS810")
      (fields (field (name "MFG") "C&K Components") (field (name "MPN") "PTS810 SJM 250 SMTR LFS"))
      (libsource (lib "KON-SU260") (part "SWITCH_PTS810"))
    )
    (comp (ref "SW2")
      (value "SWITCH_PTS810")
      (footprint "SWITCH_PTS810")
      (description "Switch, C&K, PTS810")
      (fields (field (name "MFG") "C&K Components") (field (name "MPN") "PTS810 SJM 250 SMTR LFS"))
      (libsource (lib "KON-SU260") (part "SWITCH_PTS810"))
    )
    (comp (ref "TP1")
      (value "TPTP08R")
      (footprint "TP08R")
      (description "Test pad")
      (libsource (lib "KON-SU260") (part "TPTP08R"))
    )
    (comp (ref "TP5")
      (value "TPTP08R")
      (footprint "TP08R")
      (description "Test pad")
      (libsource (lib "KON-SU260") (part "TPTP08R"))
    )
    (comp (ref "TP13")
      (value "TPTP08R")
      (footprint "TP08R")
      (description "Test pad")
      (libsource (lib "KON-SU260") (part "TPTP08R"))
    )
    (comp (ref "TP17")
      (value "TPTP08R")
      (footprint "TP08R")
      (description "Test pad")
      (libsource (lib "KON-SU260") (part "TPTP08R"))
    )
    (comp (ref "TP23")
      (value "TPTP08R")
      (footprint "TP08R")
      (description "Test pad")
      (libsource (lib "KON-SU260") (part "TPTP08R"))
    )
    (comp (ref "TP24")
      (value "TPTP08R")
      (footprint "TP08R")
      (description "Test pad")
      (libsource (lib "KON-SU260") (part "TPTP08R"))
    )
    (comp (ref "TP25")
      (value "TPTP08R")
      (footprint "TP08R")
      (description "Test pad")
      (libsource (lib "KON-SU260") (part "TPTP08R"))
    )
    (comp (ref "TP26")
      (value "TPTP08R")
      (footprint "TP08R")
      (description "Test pad")
      (libsource (lib "KON-SU260") (part "TPTP08R"))
    )
    (comp (ref "TP27")
      (value "TPTP08R")
      (footprint "TP08R")
      (description "Test pad")
      (libsource (lib "KON-SU260") (part "TPTP08R"))
    )
    (comp (ref "TP28")
      (value "TPTP08R")
      (footprint "TP08R")
      (description "Test pad")
      (libsource (lib "KON-SU260") (part "TPTP08R"))
    )
    (comp (ref "TP30")
      (value "TPTP08R")
      (footprint "TP08R")
      (description "Test pad")
      (libsource (lib "KON-SU260") (part "TPTP08R"))
    )
    (comp (ref "U$1") (value "TESTPAD") (footprint "TESTPAD") (libsource (lib "KON-SU260") (part "TESTPAD")))
    (comp (ref "U$2") (value "TESTPAD") (footprint "TESTPAD") (libsource (lib "KON-SU260") (part "TESTPAD")))
    (comp (ref "U1")
      (value "MICROCHIP_73871")
      (footprint "QFN50P400X400X80_20_pin")
      (description "Stand-alone Load Sharing and LiPo Battery Charge management controller")
      (fields (field (name "MFG") "MICROCHIP") (field (name "MPN") "MCP73871-2CCI/ML"))
      (libsource (lib "KON-SU260") (part "MICROCHIP_73871"))
    )
    (comp (ref "U2")
      (value "TPS63020")
      (footprint "QFN-14-POWERPAD3X4DSJ")
      (description "Regulator, Boost Buck, Adjustable, 3A")
      (fields (field (name "MFG") "TI") (field (name "MPN") "TPS63020DSJ"))
      (libsource (lib "KON-SU260") (part "TPS63020"))
    )
    (comp (ref "U3")
      (value "CDBQR0230L")
      (footprint "SODFL350X99-2N")
      (description "Schottky Barrier Diode, 1.5 A, 30 V, 0402 package")
      (fields
        (field (name "MFG") "Toshiba Semiconductor and Storage")
        (field (name "MPN") "CRS08(TE85L,Q,M)")
      )
      (libsource (lib "KON-SU260") (part "DIODE_SOD123F_1A"))
    )
    (comp (ref "U4")
      (value "CDBQR0230L")
      (footprint "SODFL350X99-2N")
      (description "Schottky Barrier Diode, 1.5 A, 30 V, 0402 package")
      (fields
        (field (name "MFG") "Toshiba Semiconductor and Storage")
        (field (name "MPN") "CRS08(TE85L,Q,M)")
      )
      (libsource (lib "KON-SU260") (part "DIODE_SOD123F_1A"))
    )
    (comp (ref "U5")
      (value "MK22FN1M0VLH12")
      (footprint "KON-SU260:LQFP-64N")
      (description "ARM® Cortex®-M4 Kinetis K20 Microcontroller IC 32-Bit 120MHz 1MB (1M x 8) FLASH 64-LQFP (10x10)")
      (fields (field (name "MPN") "MK22FN1M0AVLH12") (field (name "MFG") "Freescale"))
      (libsource (lib "KON-SU260") (part "MK22FN1M0VLH12"))
    )
    (comp (ref "U6")
      (value "FREESCALE_MKL17Z256VFM4")
      (footprint "KON-SU260:QFN50P50")
      (description "Microprocessor, Freescale, MKL17Z256VFM4")
      (fields
        (field (name "MFG") "FREESCALE")
        (field (name "MPN") "MKL17Z256VFM4")
        (field (name "SPI0_SS") "SPI0_SS")
        (field (name "UART2_TX") "UART2_TX")
        (field (name "SPI0_SCK") "SPI0_SCK")
        (field (name "UART2_RX") "UART2_RX")
        (field (name "SPI0_MOSI") "SPI0_MOSI")
        (field (name "SPI0_MISO") "SPI0_MISO")
        (field (name "SWD_CLK") "SWD_CLK")
        (field (name "SWD_DIO") "SWD_DIO")
        (field (name "EXTAL0") "EXTAL0")
        (field (name "XTAL0") "XTAL0")
        (field (name "LPUART0_RX") "LPUART0_RX")
        (field (name "LPUART0_TX") "LPUART0_TX")
        (field (name "I2C0_SCL") "I2C0_SCL")
        (field (name "I2C0_SDA") "I2C0_SDA")
        (field (name "LPUART1_TX") "LPUART1_TX")
        (field (name "SPI1_SS") "SPI1_SS")
        (field (name "SPI1_SCK") "SPI1_SCK")
        (field (name "SPI1_MOSI") "SPI1_MOSI")
        (field (name "MKL17Z256VFM4") "MKL17Z256VFM4")
        (field (name "SPI1_MISO") "SPI1_MISO")
        (field (name "I2C1_SCL") "I2C1_SCL")
        (field (name "I2C1_SDA") "I2C1_SDA")
        (field (name "LPUART1_RX") "LPUART1_RX")
      )
      (libsource (lib "KON-SU260") (part "FREESCALE_MKL17Z256VFM4"))
    )
    (comp (ref "U8")
      (value "VOLTAGE_TRANSLATOR_4_BIT")
      (footprint "UQFN_16")
      (description "IC, Voltage Translator, 4-bit")
      (fields (field (name "MFG") "TI") (field (name "MPN") "SN74AVC4T774RSVR"))
      (libsource (lib "KON-SU260") (part "VOLTAGE_TRANSLATOR_4_BIT"))
    )
    (comp (ref "U9")
      (value "~")
      (footprint "KON-SU260:SC70-5")
      (description "IC, Current-limited  Load Switch, Active High")
      (fields (field (name "MFG") "Texas Instruments") (field (name "MPN") "TPS22945DCKR"))
      (libsource (lib "KON-SU260") (part "TPS22945"))
    )
    (comp (ref "U10")
      (value "~")
      (footprint "REG_NCP160AMX180TBG")
      (description "IC Regulator, LDO 3.3V 0.5A, 4XDFN")
      (fields (field (name "MFG") "On Semi") (field (name "MPN") "NCP177AMX330TCG"))
      (libsource (lib "KON-SU260") (part "NCP177-D"))
    )
    (comp (ref "U16")
      (value "SARA-R410")
      (footprint "SARA")
      (fields (field (name "MFG") "U-BLOX") (field (name "MPN") "SARA-R410M-02B"))
      (libsource (lib "IoTa") (part "SARA-R410M-02B"))
    )
    (comp (ref "U19")
      (value "MAX1704X")
      (footprint "TDFN-8")
      (description "MAX17043/MAX17044: Battery Fuel Guage (43 is 1cell, 44 is 2cell)")
      (fields (field (name "MFG") "Maxim") (field (name "MPN") "MAX17043G+U"))
      (libsource (lib "KON-SU260") (part "MAX1704X"))
    )
    (comp (ref "X1")
      (value "CRYSTAL_16MHz")
      (footprint "CRYSTAL-SMD-2X1.6")
      (description "Crystal SMD, 16 MHz")
      (fields (field (name "MPN") "CX2016DB16000D0WZRC1") (field (name "MFG") "AVX"))
      (libsource (lib "KON-SU260") (part "CRYSTAL_16MHz"))
    )
    (comp (ref "X2")
      (value "32.768 kHz")
      (footprint "CRYSTAL_ABS05")
      (description "32.768kHz ±20ppm Crystal 12.5pF 90 kOhm -40°C ~ 85°C Surface Mount 2-SMD")
      (fields (field (name "MFG") "Abracon") (field (name "MPN") "ABS05-32.768KHZ-T"))
      (libsource (lib "KON-SU260") (part "CRYSTAL_32.768K_ABS05"))
    )
    (comp (ref "X3")
      (value "32.768 kHz")
      (footprint "CRYSTAL_ABS05")
      (description "32.768kHz ±20ppm Crystal 12.5pF 90 kOhm -40°C ~ 85°C Surface Mount 2-SMD")
      (fields (field (name "MFG") "Abracon") (field (name "MPN") "ABS05-32.768KHZ-T"))
      (libsource (lib "KON-SU260") (part "CRYSTAL_32.768K_ABS05"))
    )
  )
  (nets
    (net (code "1") (name "/+3.3V") (class "Default")
      (node (ref "C27") (pin "1") (pinfunction "1_1") (pintype "passive"))
      (node (ref "C28") (pin "1") (pinfunction "1_1") (pintype "passive"))
      (node (ref "C3") (pin "1") (pinfunction "1_1") (pintype "passive"))
      (node (ref "C4") (pin "1") (pinfunction "1_1") (pintype "passive"))
      (node (ref "C49") (pin "1") (pinfunction "1_1") (pintype "passive"))
      (node (ref "C7") (pin "1") (pinfunction "1_1") (pintype "passive"))
      (node (ref "C8") (pin "1") (pinfunction "1_1") (pintype "passive"))
      (node (ref "C9") (pin "1") (pinfunction "1_1") (pintype "passive"))
      (node (ref "JRIGHT") (pin "12") (pinfunction "12_12") (pintype "passive"))
      (node (ref "L1") (pin "1") (pinfunction "P$1_1") (pintype "passive"))
      (node (ref "R24") (pin "2") (pinfunction "2_2") (pintype "passive"))
      (node (ref "R35") (pin "2") (pinfunction "2_2") (pintype "passive"))
      (node (ref "R36") (pin "2") (pinfunction "2_2") (pintype "passive"))
      (node (ref "R37") (pin "2") (pinfunction "2_2") (pintype "passive"))
      (node (ref "R38") (pin "2") (pinfunction "2_2") (pintype "passive"))
      (node (ref "R40") (pin "2") (pinfunction "2_2") (pintype "passive"))
      (node (ref "R47") (pin "2") (pinfunction "2_2") (pintype "passive"))
      (node (ref "U10") (pin "1") (pinfunction "OUT_1") (pintype "passive"))
      (node (ref "U19") (pin "3") (pinfunction "VDD_3") (pintype "passive"))
      (node (ref "U5") (pin "21") (pinfunction "VBAT_21") (pintype "passive"))
      (node (ref "U5") (pin "3") (pinfunction "VDD_3") (pintype "passive"))
      (node (ref "U5") (pin "30") (pinfunction "VDD1_30") (pintype "passive"))
      (node (ref "U5") (pin "48") (pinfunction "VDD2_48") (pintype "passive"))
      (node (ref "U6") (pin "15") (pinfunction "VDD_15") (pintype "passive"))
      (node (ref "U6") (pin "7") (pinfunction "VDDA_7") (pintype "passive"))
      (node (ref "U9") (pin "5") (pinfunction "VIN_5") (pintype "passive"))
      (node (ref "smlp") (pin "1") (pinfunction "Common_ANODE_1") (pintype "passive"))
    )
    (net (code "2") (name "/+3.8V") (class "Default")
      (node (ref "C16") (pin "1") (pinfunction "1_1") (pintype "passive"))
      (node (ref "C36") (pin "1") (pinfunction "1_1") (pintype "passive"))
      (node (ref "C37") (pin "1") (pinfunction "1_1") (pintype "passive"))
      (node (ref "C38") (pin "1") (pinfunction "1_1") (pintype "passive"))
      (node (ref "L7") (pin "2") (pinfunction "P$2_2") (pintype "passive"))
      (node (ref "R13") (pin "2") (pinfunction "2_2") (pintype "passive"))
      (node (ref "TP30") (pin "TP") (pinfunction "TP_TP") (pintype "passive"))
      (node (ref "U10") (pin "3") (pinfunction "EN_3") (pintype "passive"))
      (node (ref "U10") (pin "4") (pinfunction "VIN_4") (pintype "passive"))
      (node (ref "U2") (pin "4") (pinfunction "VOUT_4") (pintype "passive"))
      (node (ref "U2") (pin "5") (pinfunction "VOUT_5") (pintype "passive"))
    )
    (net (code "3") (name "/AGND") (class "Default")
      (node (ref "C13") (pin "2") (pinfunction "2_2") (pintype "passive"))
      (node (ref "C14") (pin "2") (pinfunction "2_2") (pintype "passive"))
      (node (ref "C15") (pin "2") (pinfunction "2_2") (pintype "passive"))
      (node (ref "L3") (pin "1") (pinfunction "P$1_1") (pintype "passive"))
      (node (ref "U5") (pin "15") (pinfunction "VREFL_15") (pintype "passive"))
      (node (ref "U5") (pin "16") (pinfunction "VSSA_16") (pintype "passive"))
    )
    (net (code "4") (name "/AREF") (class "Default")
      (node (ref "C14") (pin "1") (pinfunction "1_1") (pintype "passive"))
      (node (ref "R19") (pin "2") (pinfunction "2_2") (pintype "passive"))
      (node (ref "U5") (pin "14") (pinfunction "VREFH_14") (pintype "passive"))
    )
    (net (code "5") (name "/BL_SCL") (class "Default")
      (node (ref "R40") (pin "1") (pinfunction "1_1") (pintype "passive"))
      (node (ref "U19") (pin "7") (pinfunction "SCL_7") (pintype "passive"))
      (node (ref "U5") (pin "37") (pinfunction "PTB2_37") (pintype "passive"))
      (node (ref "U6") (pin "20") (pinfunction "PTB0_20") (pintype "passive"))
    )
    (net (code "6") (name "/BL_SDA") (class "Default")
      (node (ref "R35") (pin "1") (pinfunction "1_1") (pintype "passive"))
      (node (ref "U19") (pin "8") (pinfunction "SDA_8") (pintype "passive"))
      (node (ref "U5") (pin "38") (pinfunction "PTB3_38") (pintype "passive"))
      (node (ref "U6") (pin "21") (pinfunction "PTB1_21") (pintype "passive"))
    )
    (net (code "7") (name "/CHG_PG") (class "Default")
      (node (ref "R38") (pin "1") (pinfunction "1_1") (pintype "passive"))
      (node (ref "U1") (pin "6") (pinfunction "~{PG}_6") (pintype "passive"))
      (node (ref "U6") (pin "9") (pinfunction "DAC0_OUT_PTE_30_9") (pintype "passive"))
    )
    (net (code "8") (name "/CHG_ST1") (class "Default")
      (node (ref "R37") (pin "1") (pinfunction "1_1") (pintype "passive"))
      (node (ref "U1") (pin "8") (pinfunction "STAT1/~{LBO}_8") (pintype "passive"))
      (node (ref "U6") (pin "12") (pinfunction "PTA2_12") (pintype "passive"))
    )
    (net (code "9") (name "/CHG_ST2") (class "Default")
      (node (ref "R36") (pin "1") (pinfunction "1_1") (pintype "passive"))
      (node (ref "U1") (pin "7") (pinfunction "STAT2_7") (pintype "passive"))
      (node (ref "U6") (pin "2") (pinfunction "PTE1_2") (pintype "passive"))
    )
    (net (code "10") (name "/EZP_CS") (class "Default")
      (node (ref "U5") (pin "26") (pinfunction "PTA4_26") (pintype "passive"))
      (node (ref "U6") (pin "3") (pinfunction "PTE16_3") (pintype "passive"))
    )
    (net (code "11") (name "/PWM_B") (class "Default")
      (node (ref "R21") (pin "1") (pinfunction "1_1") (pintype "passive"))
      (node (ref "U6") (pin "30") (pinfunction "PTD5_30") (pintype "passive"))
    )
    (net (code "12") (name "/PWM_G") (class "Default")
      (node (ref "R22") (pin "1") (pinfunction "1_1") (pintype "passive"))
      (node (ref "U6") (pin "29") (pinfunction "PTD4_29") (pintype "passive"))
    )
    (net (code "13") (name "/PWM_R") (class "Default")
      (node (ref "R20") (pin "1") (pinfunction "1_1") (pintype "passive"))
      (node (ref "U6") (pin "23") (pinfunction "PTC2_23") (pintype "passive"))
    )
    (net (code "14") (name "/SYS_RESET") (class "Default")
      (node (ref "JRIGHT") (pin "10") (pinfunction "10_10") (pintype "passive"))
      (node (ref "U5") (pin "41") (pinfunction "PTB18_41") (pintype "passive"))
      (node (ref "U6") (pin "19") (pinfunction "RESET_B_PTA20_19") (pintype "passive"))
    )
    (net (code "15") (name "/SYS_TCK_SWDCLK") (class "Default")
      (node (ref "JRIGHT") (pin "18") (pinfunction "18_18") (pintype "passive"))
      (node (ref "TP17") (pin "TP") (pinfunction "TP_TP") (pintype "passive"))
      (node (ref "U6") (pin "10") (pinfunction "PTA0_10") (pintype "passive"))
    )
    (net (code "16") (name "/SYS_TMS_SWDIO") (class "Default")
      (node (ref "JLEFT") (pin "18") (pinfunction "18_18") (pintype "passive"))
      (node (ref "TP27") (pin "TP") (pinfunction "TP_TP") (pintype "passive"))
      (node (ref "U6") (pin "13") (pinfunction "PTA3_13") (pintype "passive"))
    )
    (net (code "17") (name "/SYS_TX_TO_USR_RX") (class "Default")
      (node (ref "TP25") (pin "TP") (pinfunction "TP_TP") (pintype "passive"))
      (node (ref "U5") (pin "46") (pinfunction "PTC3_46") (pintype "passive"))
      (node (ref "U6") (pin "25") (pinfunction "PTC4_25") (pintype "passive"))
    )
    (net (code "18") (name "/SYS_UBLOX_RX") (class "Default")
      (node (ref "U6") (pin "31") (pinfunction "PTD6_31") (pintype "passive"))
      (node (ref "U8") (pin "P$4") (pinfunction "A4_P$4") (pintype "passive"))
    )
    (net (code "19") (name "/SYS_UBLOX_TX") (class "Default")
      (node (ref "U6") (pin "32") (pinfunction "PTD7_32") (pintype "passive"))
      (node (ref "U8") (pin "P$3") (pinfunction "A3_P$3") (pintype "passive"))
    )
    (net (code "20") (name "/SystemVin") (class "Default")
      (node (ref "C1") (pin "1") (pinfunction "1_1") (pintype "passive"))
      (node (ref "JLEFT") (pin "1") (pinfunction "1_1") (pintype "passive"))
      (node (ref "U1") (pin "17") (pinfunction "CE_17") (pintype "passive"))
      (node (ref "U1") (pin "18") (pinfunction "Vin_18") (pintype "passive"))
      (node (ref "U1") (pin "19") (pinfunction "Vin_19") (pintype "passive"))
      (node (ref "U1") (pin "2") (pinfunction "VPCC_2") (pintype "passive"))
      (node (ref "U1") (pin "3") (pinfunction "SEL_3") (pintype "passive"))
      (node (ref "U1") (pin "4") (pinfunction "PROG2_4") (pintype "passive"))
      (node (ref "U1") (pin "9") (pinfunction "~{TE}_9") (pintype "passive"))
      (node (ref "U3") (pin "CATHODE") (pinfunction "CATHODE_CATHODE") (pintype "passive"))
    )
    (net (code "21") (name "/TXL_ON_N") (class "Default")
      (node (ref "U6") (pin "1") (pinfunction "PTE0_1") (pintype "passive"))
      (node (ref "U9") (pin "4") (pinfunction "ON_4") (pintype "passive"))
    )
    (net (code "22") (name "/TXL_VCC") (class "Default")
      (node (ref "C26") (pin "1") (pinfunction "1_1") (pintype "passive"))
      (node (ref "U8") (pin "P$14") (pinfunction "VCCA_P$14") (pintype "power_in"))
      (node (ref "U8") (pin "P$15") (pinfunction "DIR1_P$15") (pintype "passive"))
      (node (ref "U8") (pin "P$5") (pinfunction "DIR3_P$5") (pintype "passive"))
      (node (ref "U9") (pin "1") (pinfunction "VOUT_1") (pintype "passive"))
    )
    (net (code "23") (name "/UBLOX_1.8V_SUPPLY") (class "Default")
      (node (ref "C25") (pin "1") (pinfunction "1_1") (pintype "passive"))
      (node (ref "U16") (pin "4") (pinfunction "V_INT$4_4") (pintype "passive"))
      (node (ref "U8") (pin "P$13") (pinfunction "VCCB_P$13") (pintype "power_in"))
    )
    (net (code "24") (name "/UBLOX_ANT") (class "Default")
      (node (ref "ANT_UFL") (pin "SIGNAL") (pinfunction "SIGNAL_SIGNAL") (pintype "passive"))
      (node (ref "U16") (pin "56") (pinfunction "ANT$56_56") (pintype "passive"))
    )
    (net (code "25") (name "/UBLOX_ANT_IND") (class "Default")
      (node (ref "U16") (pin "16") (pinfunction "GPIO1$16_16") (pintype "passive"))
    )
    (net (code "26") (name "/UBLOX_PWR_ON") (class "Default")
      (node (ref "R51") (pin "2") (pinfunction "2_2") (pintype "passive"))
      (node (ref "U16") (pin "15") (pinfunction "PWR_ON$15_15") (pintype "passive"))
      (node (ref "U6") (pin "14") (pinfunction "PTA4_14") (pintype "passive"))
    )
    (net (code "27") (name "/UBLOX_RESET") (class "Default")
      (node (ref "C43") (pin "1") (pinfunction "1_1") (pintype "passive"))
      (node (ref "U16") (pin "18") (pinfunction "RESET_N$18_18") (pintype "passive"))
      (node (ref "U6") (pin "11") (pinfunction "PTA1_11") (pintype "passive"))
    )
    (net (code "28") (name "/UBLOX_RXD") (class "Default")
      (node (ref "TP24") (pin "TP") (pinfunction "TP_TP") (pintype "passive"))
      (node (ref "U16") (pin "13") (pinfunction "RXD$13_13") (pintype "passive"))
      (node (ref "U8") (pin "P$9") (pinfunction "B4_P$9") (pintype "passive"))
    )
    (net (code "29") (name "/UBLOX_SARA_USB_D_N") (class "Default")
      (node (ref "U$2") (pin "P$1") (pinfunction "P$1_P$1") (pintype "passive"))
      (node (ref "U16") (pin "28") (pinfunction "USB_D-$28_28") (pintype "power_in"))
    )
    (net (code "30") (name "/UBLOX_SARA_USB_D_P") (class "Default")
      (node (ref "U$1") (pin "P$1") (pinfunction "P$1_P$1") (pintype "passive"))
      (node (ref "U16") (pin "29") (pinfunction "USB_D+$29_29") (pintype "power_in"))
    )
    (net (code "31") (name "/UBLOX_SIM_CLK") (class "Default")
      (node (ref "C42") (pin "1") (pinfunction "1_1") (pintype "passive"))
      (node (ref "D9") (pin "2") (pinfunction "2_2") (pintype "passive"))
      (node (ref "SIM1") (pin "C3") (pinfunction "CLK_C3") (pintype "passive"))
      (node (ref "U16") (pin "38") (pinfunction "SIM_CLK$38_38") (pintype "power_in"))
    )
    (net (code "32") (name "/UBLOX_SIM_IO") (class "Default")
      (node (ref "C44") (pin "1") (pinfunction "1_1") (pintype "passive"))
      (node (ref "D10") (pin "2") (pinfunction "2_2") (pintype "passive"))
      (node (ref "SIM1") (pin "C7") (pinfunction "IO_C7") (pintype "passive"))
      (node (ref "U16") (pin "39") (pinfunction "SIM_IO$39_39") (pintype "power_in"))
    )
    (net (code "33") (name "/UBLOX_SIM_RST") (class "Default")
      (node (ref "C41") (pin "1") (pinfunction "1_1") (pintype "passive"))
      (node (ref "D6") (pin "2") (pinfunction "2_2") (pintype "passive"))
      (node (ref "SIM1") (pin "C2") (pinfunction "RST_C2") (pintype "passive"))
      (node (ref "U16") (pin "40") (pinfunction "SIM_RST$40_40") (pintype "power_in"))
    )
    (net (code "34") (name "/UBLOX_SIM_VSIM") (class "Default")
      (node (ref "C2") (pin "1") (pinfunction "1_1") (pintype "passive"))
      (node (ref "C45") (pin "1") (pinfunction "1_1") (pintype "passive"))
      (node (ref "D11") (pin "2") (pinfunction "2_2") (pintype "passive"))
      (node (ref "SIM1") (pin "C1") (pinfunction "VCC_C1") (pintype "passive"))
      (node (ref "SIM1") (pin "C6") (pinfunction "VCC2_C6") (pintype "passive"))
      (node (ref "U16") (pin "41") (pinfunction "VSIM$41_41") (pintype "passive"))
    )
    (net (code "35") (name "/UBLOX_TXD") (class "Default")
      (node (ref "TP23") (pin "TP") (pinfunction "TP_TP") (pintype "passive"))
      (node (ref "U16") (pin "12") (pinfunction "TXD$12_12") (pintype "power_in"))
      (node (ref "U8") (pin "P$10") (pinfunction "B3_P$10") (pintype "passive"))
    )
    (net (code "36") (name "/UBLOX_VCC") (class "Default")
      (node (ref "C39") (pin "1") (pinfunction "1_1") (pintype "passive"))
      (node (ref "C40") (pin "1") (pinfunction "1_1") (pintype "passive"))
      (node (ref "C46") (pin "1") (pinfunction "1_1") (pintype "passive"))
      (node (ref "C47") (pin "1") (pinfunction "1_1") (pintype "passive"))
      (node (ref "C6") (pin "1") (pinfunction "1_1") (pintype "passive"))
      (node (ref "L7") (pin "1") (pinfunction "P$1_1") (pintype "passive"))
      (node (ref "TP28") (pin "TP") (pinfunction "TP_TP") (pintype "passive"))
      (node (ref "U16") (pin "51") (pinfunction "VCC$51_51") (pintype "power_in"))
      (node (ref "U16") (pin "52") (pinfunction "VCC$52_52") (pintype "power_in"))
      (node (ref "U16") (pin "53") (pinfunction "VCC$53_53") (pintype "power_in"))
    )
    (net (code "37") (name "/USB_5V") (class "Default")
      (node (ref "F6") (pin "1") (pinfunction "P$1_1") (pintype "passive"))
      (node (ref "J1") (pin "VCC") (pinfunction "VBUS_VCC") (pintype "passive"))
      (node (ref "TP1") (pin "TP") (pinfunction "TP_TP") (pintype "passive"))
    )
    (net (code "38") (name "/USB_D_N") (class "Default")
      (node (ref "D4") (pin "2") (pinfunction "2_2") (pintype "passive"))
      (node (ref "R1") (pin "2") (pinfunction "2_2") (pintype "passive"))
      (node (ref "U5") (pin "6") (pinfunction "USB0_DM_6") (pintype "passive"))
    )
    (net (code "39") (name "/USB_D_P") (class "Default")
      (node (ref "D3") (pin "2") (pinfunction "2_2") (pintype "passive"))
      (node (ref "R2") (pin "2") (pinfunction "2_2") (pintype "passive"))
      (node (ref "U5") (pin "5") (pinfunction "USB0_DP_5") (pintype "passive"))
    )
    (net (code "40") (name "/USB_ID") (class "Default")
      (node (ref "J1") (pin "ID") (pinfunction "ID_ID") (pintype "passive"))
      (node (ref "R66") (pin "1") (pinfunction "1_1") (pintype "passive"))
    )
    (net (code "41") (name "/USB_IN") (class "Default")
      (node (ref "C11") (pin "1") (pinfunction "1_1") (pintype "passive"))
      (node (ref "C12") (pin "1") (pinfunction "1_1") (pintype "passive"))
      (node (ref "D5") (pin "2") (pinfunction "2_2") (pintype "passive"))
      (node (ref "F6") (pin "2") (pinfunction "P$2_2") (pintype "passive"))
      (node (ref "L2") (pin "2") (pinfunction "P$2_2") (pintype "passive"))
      (node (ref "TP5") (pin "TP") (pinfunction "TP_TP") (pintype "passive"))
      (node (ref "U3") (pin "ANODE") (pinfunction "ANODE_ANODE") (pintype "passive"))
    )
    (net (code "42") (name "/USB_IN_D_N") (class "Default")
      (node (ref "J1") (pin "D-") (pinfunction "D-_D-") (pintype "passive"))
      (node (ref "R1") (pin "1") (pinfunction "1_1") (pintype "passive"))
    )
    (net (code "43") (name "/USB_IN_D_P") (class "Default")
      (node (ref "J1") (pin "D+") (pinfunction "D+_D+") (pintype "passive"))
      (node (ref "R2") (pin "1") (pinfunction "1_1") (pintype "passive"))
    )
    (net (code "44") (name "/USER01") (class "Default")
      (node (ref "JLEFT") (pin "12") (pinfunction "12_12") (pintype "passive"))
      (node (ref "U5") (pin "29") (pinfunction "PTA13_29") (pintype "passive"))
    )
    (net (code "45") (name "/USER02") (class "Default")
      (node (ref "JLEFT") (pin "11") (pinfunction "11_11") (pintype "passive"))
      (node (ref "U5") (pin "28") (pinfunction "PTA12_28") (pintype "passive"))
    )
    (net (code "46") (name "/USER03") (class "Default")
      (node (ref "JLEFT") (pin "10") (pinfunction "10_10") (pintype "passive"))
      (node (ref "U5") (pin "27") (pinfunction "PTA5_27") (pintype "passive"))
    )
    (net (code "47") (name "/USER04") (class "Default")
      (node (ref "JLEFT") (pin "3") (pinfunction "3_3") (pintype "passive"))
      (node (ref "U5") (pin "1") (pinfunction "PTE0_1") (pintype "passive"))
    )
    (net (code "48") (name "/USER05") (class "Default")
      (node (ref "JLEFT") (pin "4") (pinfunction "4_4") (pintype "passive"))
      (node (ref "U5") (pin "2") (pinfunction "PTE1_2") (pintype "passive"))
    )
    (net (code "49") (name "/USER06") (class "Default")
      (node (ref "JLEFT") (pin "13") (pinfunction "13_13") (pintype "passive"))
      (node (ref "U5") (pin "35") (pinfunction "PTB0_35") (pintype "passive"))
    )
    (net (code "50") (name "/USER07") (class "Default")
      (node (ref "JLEFT") (pin "9") (pinfunction "9_9") (pintype "passive"))
      (node (ref "U5") (pin "36") (pinfunction "PTB1_36") (pintype "passive"))
    )
    (net (code "51") (name "/USER08") (class "Default")
      (node (ref "JLEFT") (pin "14") (pinfunction "14_14") (pintype "passive"))
      (node (ref "U5") (pin "18") (pinfunction "DAC0_OUT_18") (pintype "passive"))
    )
    (net (code "52") (name "/USER09") (class "Default")
      (node (ref "JRIGHT") (pin "8") (pinfunction "8_8") (pintype "passive"))
      (node (ref "U5") (pin "45") (pinfunction "PTC2_45") (pintype "passive"))
    )
    (net (code "53") (name "/USER10") (class "Default")
      (node (ref "JRIGHT") (pin "7") (pinfunction "7_7") (pintype "passive"))
      (node (ref "U5") (pin "44") (pinfunction "PTC1_44") (pintype "passive"))
    )
    (net (code "54") (name "/USER11") (class "Default")
      (node (ref "JRIGHT") (pin "9") (pinfunction "9_9") (pintype "passive"))
      (node (ref "U5") (pin "43") (pinfunction "PTC0_43") (pintype "passive"))
    )
    (net (code "55") (name "/USER12") (class "Default")
      (node (ref "JRIGHT") (pin "6") (pinfunction "6_6") (pintype "passive"))
      (node (ref "U5") (pin "53") (pinfunction "PTC8_53") (pintype "passive"))
    )
    (net (code "56") (name "/USER13") (class "Default")
      (node (ref "JLEFT") (pin "5") (pinfunction "5_5") (pintype "passive"))
      (node (ref "U5") (pin "58") (pinfunction "PTD1_58") (pintype "passive"))
    )
    (net (code "57") (name "/USER14") (class "Default")
      (node (ref "JLEFT") (pin "6") (pinfunction "6_6") (pintype "passive"))
      (node (ref "U5") (pin "59") (pinfunction "PTD2_59") (pintype "passive"))
    )
    (net (code "58") (name "/USER15") (class "Default")
      (node (ref "JLEFT") (pin "8") (pinfunction "8_8") (pintype "passive"))
      (node (ref "U5") (pin "60") (pinfunction "PTD3_60") (pintype "passive"))
    )
    (net (code "59") (name "/USER16") (class "Default")
      (node (ref "JRIGHT") (pin "4") (pinfunction "4_4") (pintype "passive"))
      (node (ref "U5") (pin "61") (pinfunction "PTD4_61") (pintype "passive"))
    )
    (net (code "60") (name "/USER17") (class "Default")
      (node (ref "JLEFT") (pin "7") (pinfunction "7_7") (pintype "passive"))
      (node (ref "U5") (pin "62") (pinfunction "PTD5_62") (pintype "passive"))
    )
    (net (code "61") (name "/USER18") (class "Default")
      (node (ref "JRIGHT") (pin "5") (pinfunction "5_5") (pintype "passive"))
      (node (ref "U5") (pin "63") (pinfunction "PTD6_63") (pintype "passive"))
    )
    (net (code "62") (name "/USER19") (class "Default")
      (node (ref "JRIGHT") (pin "3") (pinfunction "3_3") (pintype "passive"))
      (node (ref "U5") (pin "64") (pinfunction "PTD7_64") (pintype "passive"))
    )
    (net (code "63") (name "/USER23") (class "Default")
      (node (ref "JRIGHT") (pin "13") (pinfunction "13_13") (pintype "passive"))
      (node (ref "U5") (pin "51") (pinfunction "PTC6_51") (pintype "passive"))
    )
    (net (code "64") (name "/USER24") (class "Default")
      (node (ref "JRIGHT") (pin "14") (pinfunction "14_14") (pintype "passive"))
      (node (ref "U5") (pin "52") (pinfunction "PTC7_52") (pintype "passive"))
    )
    (net (code "65") (name "/USER26") (class "Default")
      (node (ref "JRIGHT") (pin "15") (pinfunction "15_15") (pintype "passive"))
      (node (ref "U5") (pin "55") (pinfunction "PTC10_55") (pintype "passive"))
    )
    (net (code "66") (name "/USER27") (class "Default")
      (node (ref "JRIGHT") (pin "17") (pinfunction "17_17") (pintype "passive"))
      (node (ref "U5") (pin "56") (pinfunction "PTC11_56") (pintype "passive"))
    )
    (net (code "67") (name "/USER28") (class "Default")
      (node (ref "JRIGHT") (pin "16") (pinfunction "16_16") (pintype "passive"))
      (node (ref "U5") (pin "57") (pinfunction "PTD0_57") (pintype "passive"))
    )
    (net (code "68") (name "/USER_PROGRAM") (class "Default")
      (node (ref "JRIGHT") (pin "11") (pinfunction "11_11") (pintype "passive"))
      (node (ref "R24") (pin "1") (pinfunction "1_1") (pintype "passive"))
      (node (ref "SW2") (pin "1") (pinfunction "P$1_1") (pintype "passive"))
      (node (ref "SW2") (pin "2") (pinfunction "P$1_2") (pintype "passive"))
      (node (ref "U5") (pin "54") (pinfunction "PTC9_54") (pintype "passive"))
      (node (ref "U6") (pin "27") (pinfunction "PTC6_27") (pintype "passive"))
    )
    (net (code "69") (name "/USR_LED") (class "Default")
      (node (ref "D1") (pin "ANODE") (pinfunction "ANODE_ANODE") (pintype "passive"))
      (node (ref "U5") (pin "42") (pinfunction "PTB19_42") (pintype "passive"))
    )
    (net (code "70") (name "/USR_RESET") (class "Default")
      (node (ref "C24") (pin "1") (pinfunction "1_1") (pintype "passive"))
      (node (ref "JLEFT") (pin "15") (pinfunction "15_15") (pintype "passive"))
      (node (ref "R47") (pin "1") (pinfunction "1_1") (pintype "passive"))
      (node (ref "SW1") (pin "1") (pinfunction "P$1_1") (pintype "passive"))
      (node (ref "SW1") (pin "2") (pinfunction "P$1_2") (pintype "passive"))
      (node (ref "U5") (pin "34") (pinfunction "RESET_B_34") (pintype "passive"))
      (node (ref "U6") (pin "26") (pinfunction "PTC5_26") (pintype "passive"))
    )
    (net (code "71") (name "/USR_TCK_SWDCLK") (class "Default")
      (node (ref "JLEFT") (pin "17") (pinfunction "17_17") (pintype "passive"))
      (node (ref "U5") (pin "22") (pinfunction "PTA0_22") (pintype "passive"))
      (node (ref "U6") (pin "4") (pinfunction "PTE17_4") (pintype "passive"))
    )
    (net (code "72") (name "/USR_TDI") (class "Default")
      (node (ref "R66") (pin "2") (pinfunction "2_2") (pintype "passive"))
      (node (ref "U5") (pin "23") (pinfunction "PTA1_23") (pintype "passive"))
      (node (ref "U6") (pin "5") (pinfunction "PTE18_5") (pintype "passive"))
    )
    (net (code "73") (name "/USR_TDO_SWO") (class "Default")
      (node (ref "U5") (pin "24") (pinfunction "PTA2_24") (pintype "passive"))
      (node (ref "U6") (pin "6") (pinfunction "PTE19_6") (pintype "passive"))
    )
    (net (code "74") (name "/USR_TMS_SWDIO") (class "Default")
      (node (ref "JLEFT") (pin "16") (pinfunction "16_16") (pintype "passive"))
      (node (ref "U5") (pin "25") (pinfunction "PTA3_25") (pintype "passive"))
      (node (ref "U6") (pin "22") (pinfunction "PTC1_22") (pintype "passive"))
    )
    (net (code "75") (name "/USR_TX_TO_SYS_RX") (class "Default")
      (node (ref "TP26") (pin "TP") (pinfunction "TP_TP") (pintype "passive"))
      (node (ref "U5") (pin "49") (pinfunction "PTC4_49") (pintype "passive"))
      (node (ref "U6") (pin "24") (pinfunction "PTC3_24") (pintype "passive"))
    )
    (net (code "76") (name "/VBATT") (class "Default")
      (node (ref "J20") (pin "BAT") (pinfunction "BAT_BAT") (pintype "passive"))
      (node (ref "R45") (pin "2") (pinfunction "2_2") (pintype "passive"))
      (node (ref "TP13") (pin "TP") (pinfunction "TP_TP") (pintype "passive"))
      (node (ref "U1") (pin "14") (pinfunction "Vbat_14") (pintype "passive"))
      (node (ref "U1") (pin "15") (pinfunction "Vbat_15") (pintype "passive"))
      (node (ref "U1") (pin "16") (pinfunction "Vbat_16") (pintype "passive"))
    )
    (net (code "77") (name "/VOUT33") (class "Default")
      (node (ref "C10") (pin "1") (pinfunction "1_1") (pintype "passive"))
      (node (ref "U5") (pin "7") (pinfunction "VOUT33_7") (pintype "passive"))
    )
    (net (code "78") (name "/VREGIN") (class "Default")
      (node (ref "C18") (pin "1") (pinfunction "1_1") (pintype "passive"))
      (node (ref "U4") (pin "CATHODE") (pinfunction "CATHODE_CATHODE") (pintype "passive"))
      (node (ref "U5") (pin "8") (pinfunction "VREGIN_8") (pintype "passive"))
    )
    (net (code "79") (name "/VSystem") (class "Default")
      (node (ref "C33") (pin "1") (pinfunction "1_1") (pintype "passive"))
      (node (ref "C34") (pin "1") (pinfunction "1_1") (pintype "passive"))
      (node (ref "D8") (pin "ANODE") (pinfunction "ANODE_ANODE") (pintype "passive"))
      (node (ref "U1") (pin "1") (pinfunction "OUT_1") (pintype "passive"))
      (node (ref "U1") (pin "20") (pinfunction "OUT_20") (pintype "passive"))
      (node (ref "U2") (pin "10") (pinfunction "VIN_10") (pintype "passive"))
      (node (ref "U2") (pin "11") (pinfunction "VIN_11") (pintype "passive"))
    )
    (net (code "80") (name "/VSystem_User") (class "Default")
      (node (ref "D8") (pin "CATHODE") (pinfunction "CATHODE_CATHODE") (pintype "passive"))
      (node (ref "JRIGHT") (pin "1") (pinfunction "1_1") (pintype "passive"))
    )
    (net (code "81") (name "/WAKE_USR") (class "Default")
      (node (ref "D7") (pin "ANODE") (pinfunction "ANODE_ANODE") (pintype "passive"))
      (node (ref "U5") (pin "50") (pinfunction "PTC5_50") (pintype "passive"))
      (node (ref "U6") (pin "28") (pinfunction "PTC7_28") (pintype "passive"))
    )
    (net (code "82") (name "GND") (class "Default")
      (node (ref "ANT_UFL") (pin "GND1") (pinfunction "GND1_GND1") (pintype "passive"))
      (node (ref "ANT_UFL") (pin "GND2") (pinfunction "GND2_GND2") (pintype "passive"))
      (node (ref "ANT_UFL") (pin "GND3") (pinfunction "GND3_GND3") (pintype "passive"))
      (node (ref "C1") (pin "2") (pinfunction "2_2") (pintype "passive"))
      (node (ref "C10") (pin "2") (pinfunction "2_2") (pintype "passive"))
      (node (ref "C11") (pin "2") (pinfunction "2_2") (pintype "passive"))
      (node (ref "C12") (pin "2") (pinfunction "2_2") (pintype "passive"))
      (node (ref "C16") (pin "2") (pinfunction "2_2") (pintype "passive"))
      (node (ref "C18") (pin "2") (pinfunction "2_2") (pintype "passive"))
      (node (ref "C2") (pin "2") (pinfunction "2_2") (pintype "passive"))
      (node (ref "C20") (pin "2") (pinfunction "2_2") (pintype "passive"))
      (node (ref "C24") (pin "2") (pinfunction "2_2") (pintype "passive"))
      (node (ref "C25") (pin "2") (pinfunction "2_2") (pintype "passive"))
      (node (ref "C26") (pin "2") (pinfunction "2_2") (pintype "passive"))
      (node (ref "C27") (pin "2") (pinfunction "2_2") (pintype "passive"))
      (node (ref "C28") (pin "2") (pinfunction "2_2") (pintype "passive"))
      (node (ref "C3") (pin "2") (pinfunction "2_2") (pintype "passive"))
      (node (ref "C33") (pin "2") (pinfunction "2_2") (pintype "passive"))
      (node (ref "C34") (pin "2") (pinfunction "2_2") (pintype "passive"))
      (node (ref "C36") (pin "2") (pinfunction "2_2") (pintype "passive"))
      (node (ref "C37") (pin "2") (pinfunction "2_2") (pintype "passive"))
      (node (ref "C38") (pin "2") (pinfunction "2_2") (pintype "passive"))
      (node (ref "C39") (pin "2") (pinfunction "2_2") (pintype "passive"))
      (node (ref "C4") (pin "2") (pinfunction "2_2") (pintype "passive"))
      (node (ref "C40") (pin "2") (pinfunction "2_2") (pintype "passive"))
      (node (ref "C41") (pin "2") (pinfunction "2_2") (pintype "passive"))
      (node (ref "C42") (pin "2") (pinfunction "2_2") (pintype "passive"))
      (node (ref "C43") (pin "2") (pinfunction "2_2") (pintype "passive"))
      (node (ref "C44") (pin "2") (pinfunction "2_2") (pintype "passive"))
      (node (ref "C45") (pin "2") (pinfunction "2_2") (pintype "passive"))
      (node (ref "C46") (pin "2") (pinfunction "2_2") (pintype "passive"))
      (node (ref "C47") (pin "2") (pinfunction "2_2") (pintype "passive"))
      (node (ref "C48") (pin "2") (pinfunction "2_2") (pintype "passive"))
      (node (ref "C49") (pin "2") (pinfunction "2_2") (pintype "passive"))
      (node (ref "C6") (pin "2") (pinfunction "2_2") (pintype "passive"))
      (node (ref "C7") (pin "2") (pinfunction "2_2") (pintype "passive"))
      (node (ref "C8") (pin "2") (pinfunction "2_2") (pintype "passive"))
      (node (ref "C9") (pin "2") (pinfunction "2_2") (pintype "passive"))
      (node (ref "D10") (pin "1") (pinfunction "1_1") (pintype "passive"))
      (node (ref "D11") (pin "1") (pinfunction "1_1") (pintype "passive"))
      (node (ref "D3") (pin "1") (pinfunction "1_1") (pintype "passive"))
      (node (ref "D4") (pin "1") (pinfunction "1_1") (pintype "passive"))
      (node (ref "D5") (pin "1") (pinfunction "1_1") (pintype "passive"))
      (node (ref "D6") (pin "1") (pinfunction "1_1") (pintype "passive"))
      (node (ref "D9") (pin "1") (pinfunction "1_1") (pintype "passive"))
      (node (ref "J1") (pin "GND") (pinfunction "GND_GND") (pintype "passive"))
      (node (ref "J20") (pin "CHASSIS1") (pinfunction "CHASSIS_1_CHASSIS1") (pintype "passive"))
      (node (ref "J20") (pin "CHASSIS2") (pinfunction "CHASSIS_2_CHASSIS2") (pintype "passive"))
      (node (ref "J20") (pin "GND") (pinfunction "GND_GND") (pintype "passive"))
      (node (ref "JLEFT") (pin "2") (pinfunction "2_2") (pintype "passive"))
      (node (ref "JRIGHT") (pin "2") (pinfunction "2_2") (pintype "passive"))
      (node (ref "L3") (pin "2") (pinfunction "P$2_2") (pintype "passive"))
      (node (ref "R12") (pin "2") (pinfunction "2_2") (pintype "passive"))
      (node (ref "R2000") (pin "1") (pinfunction "1_1") (pintype "passive"))
      (node (ref "R26") (pin "1") (pinfunction "1_1") (pintype "passive"))
      (node (ref "R51") (pin "1") (pinfunction "1_1") (pintype "passive"))
      (node (ref "R65") (pin "1") (pinfunction "1_1") (pintype "passive"))
      (node (ref "R7") (pin "1") (pinfunction "1_1") (pintype "passive"))
      (node (ref "R8") (pin "1") (pinfunction "1_1") (pintype "passive"))
      (node (ref "SIM1") (pin "C5") (pinfunction "GND_C5") (pintype "passive"))
      (node (ref "SW1") (pin "3") (pinfunction "P$1_3") (pintype "passive"))
      (node (ref "SW1") (pin "4") (pinfunction "P$2_4") (pintype "passive"))
      (node (ref "SW2") (pin "3") (pinfunction "P$1_3") (pintype "passive"))
      (node (ref "SW2") (pin "4") (pinfunction "P$2_4") (pintype "passive"))
      (node (ref "U1") (pin "10") (pinfunction "Vss_10") (pintype "passive"))
      (node (ref "U1") (pin "11") (pinfunction "Vss_11") (pintype "passive"))
      (node (ref "U1") (pin "21") (pinfunction "Vss_21") (pintype "passive"))
      (node (ref "U10") (pin "2") (pinfunction "GND_2") (pintype "passive"))
      (node (ref "U10") (pin "5") (pinfunction "GND_5") (pintype "passive"))
      (node (ref "U16") (pin "1") (pinfunction "GND$1_1") (pintype "passive"))
      (node (ref "U16") (pin "10") (pinfunction "RTS$10_10") (pintype "passive"))
      (node (ref "U16") (pin "14") (pinfunction "GND$14_14") (pintype "passive"))
      (node (ref "U16") (pin "20") (pinfunction "GND$20_20") (pintype "passive"))
      (node (ref "U16") (pin "21") (pinfunction "GND$21_21") (pintype "passive"))
      (node (ref "U16") (pin "22") (pinfunction "GND$22_22") (pintype "power_in"))
      (node (ref "U16") (pin "3") (pinfunction "GND$3_3") (pintype "passive"))
      (node (ref "U16") (pin "30") (pinfunction "GND$30_30") (pintype "passive"))
      (node (ref "U16") (pin "32") (pinfunction "GND$32_32") (pintype "power_in"))
      (node (ref "U16") (pin "33") (pinfunction "RSVD$33_33") (pintype "power_in"))
      (node (ref "U16") (pin "43") (pinfunction "GND$43_43") (pintype "passive"))
      (node (ref "U16") (pin "5") (pinfunction "GND$5_5") (pintype "passive"))
      (node (ref "U16") (pin "50") (pinfunction "GND$50_50") (pintype "power_in"))
      (node (ref "U16") (pin "54") (pinfunction "GND$54_54") (pintype "power_in"))
      (node (ref "U16") (pin "55") (pinfunction "GND$55_55") (pintype "power_in"))
      (node (ref "U16") (pin "57") (pinfunction "GND$57_57") (pintype "power_in"))
      (node (ref "U16") (pin "58") (pinfunction "GND$58_58") (pintype "power_in"))
      (node (ref "U16") (pin "59") (pinfunction "GND$59_59") (pintype "power_in"))
      (node (ref "U16") (pin "60") (pinfunction "GND$60_60") (pintype "power_in"))
      (node (ref "U16") (pin "61") (pinfunction "GND$61_61") (pintype "power_in"))
      (node (ref "U16") (pin "63") (pinfunction "GND$63_63") (pintype "power_in"))
      (node (ref "U16") (pin "64") (pinfunction "GND$64_64") (pintype "power_in"))
      (node (ref "U16") (pin "65") (pinfunction "GND$65_65") (pintype "power_in"))
      (node (ref "U16") (pin "66") (pinfunction "GND$66_66") (pintype "power_in"))
      (node (ref "U16") (pin "67") (pinfunction "GND$67_67") (pintype "passive"))
      (node (ref "U16") (pin "68") (pinfunction "GND$68_68") (pintype "passive"))
      (node (ref "U16") (pin "69") (pinfunction "GND$69_69") (pintype "passive"))
      (node (ref "U16") (pin "70") (pinfunction "GND$70_70") (pintype "passive"))
      (node (ref "U16") (pin "71") (pinfunction "GND$71_71") (pintype "passive"))
      (node (ref "U16") (pin "72") (pinfunction "GND$72_72") (pintype "passive"))
      (node (ref "U16") (pin "73") (pinfunction "GND$73_73") (pintype "passive"))
      (node (ref "U16") (pin "74") (pinfunction "GND$74_74") (pintype "passive"))
      (node (ref "U16") (pin "75") (pinfunction "GND$75_75") (pintype "passive"))
      (node (ref "U16") (pin "76") (pinfunction "GND$76_76") (pintype "passive"))
      (node (ref "U16") (pin "77") (pinfunction "GND$77_77") (pintype "passive"))
      (node (ref "U16") (pin "78") (pinfunction "GND$78_78") (pintype "passive"))
      (node (ref "U16") (pin "79") (pinfunction "GND$79_79") (pintype "passive"))
      (node (ref "U16") (pin "80") (pinfunction "GND$80_80") (pintype "passive"))
      (node (ref "U16") (pin "81") (pinfunction "GND$81_81") (pintype "passive"))
      (node (ref "U16") (pin "82") (pinfunction "GND$82_82") (pintype "passive"))
      (node (ref "U16") (pin "83") (pinfunction "GND$83_83") (pintype "passive"))
      (node (ref "U16") (pin "84") (pinfunction "GND$84_84") (pintype "passive"))
      (node (ref "U16") (pin "85") (pinfunction "GND$85_85") (pintype "passive"))
      (node (ref "U16") (pin "86") (pinfunction "GND$86_86") (pintype "passive"))
      (node (ref "U16") (pin "87") (pinfunction "GND$87_87") (pintype "passive"))
      (node (ref "U16") (pin "88") (pinfunction "GND$88_88") (pintype "passive"))
      (node (ref "U16") (pin "89") (pinfunction "GND$89_89") (pintype "passive"))
      (node (ref "U16") (pin "9") (pinfunction "DTR$9_9") (pintype "passive"))
      (node (ref "U16") (pin "90") (pinfunction "GND$90_90") (pintype "passive"))
      (node (ref "U16") (pin "91") (pinfunction "GND$91_91") (pintype "passive"))
      (node (ref "U16") (pin "92") (pinfunction "GND$92_92") (pintype "passive"))
      (node (ref "U16") (pin "93") (pinfunction "GND$93_93") (pintype "passive"))
      (node (ref "U16") (pin "94") (pinfunction "GND$94_94") (pintype "passive"))
      (node (ref "U16") (pin "95") (pinfunction "GND$95_95") (pintype "passive"))
      (node (ref "U16") (pin "96") (pinfunction "GND$96_96") (pintype "passive"))
      (node (ref "U19") (pin "1") (pinfunction "CTG_1") (pintype "passive"))
      (node (ref "U19") (pin "4") (pinfunction "GND_4") (pintype "passive"))
      (node (ref "U19") (pin "6") (pinfunction "QST_6") (pintype "passive"))
      (node (ref "U19") (pin "EP") (pinfunction "GND_EP") (pintype "passive"))
      (node (ref "U2") (pin "13") (pinfunction "PS/SYNC_13") (pintype "passive"))
      (node (ref "U2") (pin "2") (pinfunction "GND_2") (pintype "passive"))
      (node (ref "U2") (pin "POWERPAD") (pinfunction "PGND_POWERPAD") (pintype "passive"))
      (node (ref "U5") (pin "31") (pinfunction "VSS_31") (pintype "passive"))
      (node (ref "U5") (pin "4") (pinfunction "VSS_4") (pintype "passive"))
      (node (ref "U5") (pin "47") (pinfunction "VSS_47") (pintype "passive"))
      (node (ref "U6") (pin "16") (pinfunction "VSS_16") (pintype "passive"))
      (node (ref "U6") (pin "8") (pinfunction "VSSA_8") (pintype "passive"))
      (node (ref "U6") (pin "PAD") (pinfunction "VSS_PAD") (pintype "passive"))
      (node (ref "U8") (pin "P$1") (pinfunction "A1_P$1") (pintype "passive"))
      (node (ref "U8") (pin "P$11") (pinfunction "B2_P$11") (pintype "passive"))
      (node (ref "U8") (pin "P$16") (pinfunction "DIR2_P$16") (pintype "passive"))
      (node (ref "U8") (pin "P$6") (pinfunction "DIR4_P$6") (pintype "passive"))
      (node (ref "U8") (pin "P$7") (pinfunction "~OE_P$7") (pintype "passive"))
      (node (ref "U8") (pin "P$8") (pinfunction "GND_P$8") (pintype "passive"))
      (node (ref "U9") (pin "2") (pinfunction "GND_2") (pintype "passive"))
      (node (ref "X1") (pin "2") (pinfunction "2_2") (pintype "passive"))
      (node (ref "X1") (pin "4") (pinfunction "2_4") (pintype "passive"))
    )
    (net (code "83") (name "Net-(D1-PadCATHODE)") (class "Default")
      (node (ref "D1") (pin "CATHODE") (pinfunction "CATHODE_CATHODE") (pintype "passive"))
      (node (ref "R26") (pin "2") (pinfunction "2_2") (pintype "passive"))
    )
    (net (code "84") (name "Net-(D7-PadCATHODE)") (class "Default")
      (node (ref "D7") (pin "CATHODE") (pinfunction "CATHODE_CATHODE") (pintype "passive"))
      (node (ref "R65") (pin "2") (pinfunction "2_2") (pintype "passive"))
    )
    (net (code "85") (name "Net-(L1-P$2)") (class "Default")
      (node (ref "C13") (pin "1") (pinfunction "1_1") (pintype "passive"))
      (node (ref "L1") (pin "2") (pinfunction "P$2_2") (pintype "passive"))
      (node (ref "R19") (pin "1") (pinfunction "1_1") (pintype "passive"))
      (node (ref "U5") (pin "13") (pinfunction "VDDA_13") (pintype "passive"))
    )
    (net (code "86") (name "Net-(L2-P$1)") (class "Default")
      (node (ref "L2") (pin "1") (pinfunction "P$1_1") (pintype "passive"))
      (node (ref "U4") (pin "ANODE") (pinfunction "ANODE_ANODE") (pintype "passive"))
    )
    (net (code "87") (name "Net-(L5-PadP$1)") (class "Default")
      (node (ref "L5") (pin "P$1") (pinfunction "P$1_P$1") (pintype "passive"))
      (node (ref "U2") (pin "8") (pinfunction "L1_8") (pintype "passive"))
      (node (ref "U2") (pin "9") (pinfunction "L1_9") (pintype "passive"))
    )
    (net (code "88") (name "Net-(L5-PadP$2)") (class "Default")
      (node (ref "L5") (pin "P$2") (pinfunction "P$2_P$2") (pintype "passive"))
      (node (ref "U2") (pin "6") (pinfunction "L2_6") (pintype "passive"))
      (node (ref "U2") (pin "7") (pinfunction "L2_7") (pintype "passive"))
    )
    (net (code "89") (name "Net-(U1-PROG1)") (class "Default")
      (node (ref "R8") (pin "2") (pinfunction "2_2") (pintype "passive"))
      (node (ref "U1") (pin "13") (pinfunction "PROG1_13") (pintype "passive"))
    )
    (net (code "90") (name "Net-(U1-PROG3)") (class "Default")
      (node (ref "R7") (pin "2") (pinfunction "2_2") (pintype "passive"))
      (node (ref "U1") (pin "12") (pinfunction "PROG3_12") (pintype "passive"))
    )
    (net (code "91") (name "Net-(U1-Therm)") (class "Default")
      (node (ref "R2000") (pin "2") (pinfunction "2_2") (pintype "passive"))
      (node (ref "U1") (pin "5") (pinfunction "Therm_5") (pintype "passive"))
    )
    (net (code "92") (name "Net-(U2-EN)") (class "Default")
      (node (ref "C48") (pin "1") (pinfunction "1_1") (pintype "passive"))
      (node (ref "U2") (pin "1") (pinfunction "VINA_1") (pintype "passive"))
      (node (ref "U2") (pin "12") (pinfunction "EN_12") (pintype "passive"))
    )
    (net (code "93") (name "Net-(U2-FB)") (class "Default")
      (node (ref "R12") (pin "1") (pinfunction "1_1") (pintype "passive"))
      (node (ref "R13") (pin "1") (pinfunction "1_1") (pintype "passive"))
      (node (ref "U2") (pin "3") (pinfunction "FB_3") (pintype "passive"))
    )
    (net (code "94") (name "Net-(U5-EXTAL32)") (class "Default")
      (node (ref "U5") (pin "20") (pinfunction "EXTAL32_20") (pintype "passive"))
      (node (ref "X2") (pin "1") (pinfunction "XTAL1_1") (pintype "passive"))
    )
    (net (code "95") (name "Net-(U5-PTA18)") (class "Default")
      (node (ref "U5") (pin "32") (pinfunction "PTA18_32") (pintype "passive"))
      (node (ref "X1") (pin "1") (pinfunction "1_1") (pintype "passive"))
    )
    (net (code "96") (name "Net-(U5-PTA19)") (class "Default")
      (node (ref "U5") (pin "33") (pinfunction "PTA19_33") (pintype "passive"))
      (node (ref "X1") (pin "3") (pinfunction "3_3") (pintype "passive"))
    )
    (net (code "97") (name "Net-(U5-VREF_OUT)") (class "Default")
      (node (ref "C15") (pin "1") (pinfunction "1_1") (pintype "passive"))
      (node (ref "U5") (pin "17") (pinfunction "VREF_OUT_17") (pintype "passive"))
    )
    (net (code "98") (name "Net-(U5-XTAL32)") (class "Default")
      (node (ref "U5") (pin "19") (pinfunction "XTAL32_19") (pintype "passive"))
      (node (ref "X2") (pin "2") (pinfunction "XTAL2_2") (pintype "passive"))
    )
    (net (code "99") (name "Net-(U6-PTA18)") (class "Default")
      (node (ref "U6") (pin "17") (pinfunction "PTA18_17") (pintype "passive"))
      (node (ref "X3") (pin "2") (pinfunction "XTAL2_2") (pintype "passive"))
    )
    (net (code "100") (name "Net-(U6-PTA19)") (class "Default")
      (node (ref "U6") (pin "18") (pinfunction "PTA19_18") (pintype "passive"))
      (node (ref "X3") (pin "1") (pinfunction "XTAL1_1") (pintype "passive"))
    )
    (net (code "101") (name "Net-(U19-CELL)") (class "Default")
      (node (ref "C20") (pin "1") (pinfunction "1_1") (pintype "passive"))
      (node (ref "R45") (pin "1") (pinfunction "1_1") (pintype "passive"))
      (node (ref "U19") (pin "2") (pinfunction "CELL_2") (pintype "passive"))
    )
    (net (code "102") (name "Net-(smlp-CATHODE_B)") (class "Default")
      (node (ref "R21") (pin "2") (pinfunction "2_2") (pintype "passive"))
      (node (ref "smlp") (pin "3") (pinfunction "CATHODE_B_3") (pintype "passive"))
    )
    (net (code "103") (name "Net-(smlp-CATHODE_G)") (class "Default")
      (node (ref "R22") (pin "2") (pinfunction "2_2") (pintype "passive"))
      (node (ref "smlp") (pin "4") (pinfunction "CATHODE_G_4") (pintype "passive"))
    )
    (net (code "104") (name "Net-(smlp-CATHODE_R)") (class "Default")
      (node (ref "R20") (pin "2") (pinfunction "2_2") (pintype "passive"))
      (node (ref "smlp") (pin "2") (pinfunction "CATHODE_R_2") (pintype "passive"))
    )
    (net (code "105") (name "unconnected-(SIM1-NC1-PadMTG1)") (class "Default")
      (node (ref "SIM1") (pin "MTG1") (pinfunction "NC1_MTG1") (pintype "passive"))
    )
    (net (code "106") (name "unconnected-(SIM1-NC2-PadMTG2)") (class "Default")
      (node (ref "SIM1") (pin "MTG2") (pinfunction "NC2_MTG2") (pintype "passive"))
    )
    (net (code "107") (name "unconnected-(U2-PG-Pad14)") (class "Default")
      (node (ref "U2") (pin "14") (pinfunction "PG_14") (pintype "passive"))
    )
    (net (code "108") (name "unconnected-(U5-PGA0_DM-Pad10)") (class "Default")
      (node (ref "U5") (pin "10") (pinfunction "PGA0_DM_10") (pintype "passive"))
    )
    (net (code "109") (name "unconnected-(U5-PGA0_DP-Pad9)") (class "Default")
      (node (ref "U5") (pin "9") (pinfunction "PGA0_DP_9") (pintype "passive"))
    )
    (net (code "110") (name "unconnected-(U5-PGA1_DM-Pad12)") (class "Default")
      (node (ref "U5") (pin "12") (pinfunction "PGA1_DM_12") (pintype "passive"))
    )
    (net (code "111") (name "unconnected-(U5-PGA1_DP-Pad11)") (class "Default")
      (node (ref "U5") (pin "11") (pinfunction "PGA1_DP_11") (pintype "passive"))
    )
    (net (code "112") (name "unconnected-(U5-PTB16-Pad39)") (class "Default")
      (node (ref "U5") (pin "39") (pinfunction "PTB16_39") (pintype "passive"))
    )
    (net (code "113") (name "unconnected-(U5-PTB17-Pad40)") (class "Default")
      (node (ref "U5") (pin "40") (pinfunction "PTB17_40") (pintype "passive"))
    )
    (net (code "114") (name "unconnected-(U8-A2-PadP$2)") (class "Default")
      (node (ref "U8") (pin "P$2") (pinfunction "A2_P$2") (pintype "passive+no_connect"))
    )
    (net (code "115") (name "unconnected-(U8-B1-PadP$12)") (class "Default")
      (node (ref "U8") (pin "P$12") (pinfunction "B1_P$12") (pintype "passive+no_connect"))
    )
    (net (code "116") (name "unconnected-(U9-OC-Pad3)") (class "Default")
      (node (ref "U9") (pin "3") (pinfunction "OC_3") (pintype "passive+no_connect"))
    )
    (net (code "117") (name "unconnected-(U16-ANT_DET$62-Pad62)") (class "Default")
      (node (ref "U16") (pin "62") (pinfunction "ANT_DET$62_62") (pintype "passive"))
    )
    (net (code "118") (name "unconnected-(U16-CTS$11-Pad11)") (class "Default")
      (node (ref "U16") (pin "11") (pinfunction "CTS$11_11") (pintype "passive+no_connect"))
    )
    (net (code "119") (name "unconnected-(U16-DCD$8-Pad8)") (class "Default")
      (node (ref "U16") (pin "8") (pinfunction "DCD$8_8") (pintype "passive"))
    )
    (net (code "120") (name "unconnected-(U16-DSR$6-Pad6)") (class "Default")
      (node (ref "U16") (pin "6") (pinfunction "DSR$6_6") (pintype "passive"))
    )
    (net (code "121") (name "unconnected-(U16-GPIO2$23-Pad23)") (class "Default")
      (node (ref "U16") (pin "23") (pinfunction "GPIO2$23_23") (pintype "power_in"))
    )
    (net (code "122") (name "unconnected-(U16-GPIO3$24-Pad24)") (class "Default")
      (node (ref "U16") (pin "24") (pinfunction "GPIO3$24_24") (pintype "passive"))
    )
    (net (code "123") (name "unconnected-(U16-GPIO4$25-Pad25)") (class "Default")
      (node (ref "U16") (pin "25") (pinfunction "GPIO4$25_25") (pintype "power_in"))
    )
    (net (code "124") (name "unconnected-(U16-GPIO5$42-Pad42)") (class "Default")
      (node (ref "U16") (pin "42") (pinfunction "GPIO5$42_42") (pintype "passive"))
    )
    (net (code "125") (name "unconnected-(U16-GPIO6$19-Pad19)") (class "Default")
      (node (ref "U16") (pin "19") (pinfunction "GPIO6$19_19") (pintype "passive"))
    )
    (net (code "126") (name "unconnected-(U16-I2S_CLK$36-Pad36)") (class "Default")
      (node (ref "U16") (pin "36") (pinfunction "I2S_CLK$36_36") (pintype "passive"))
    )
    (net (code "127") (name "unconnected-(U16-I2S_RXD$37-Pad37)") (class "Default")
      (node (ref "U16") (pin "37") (pinfunction "I2S_RXD$37_37") (pintype "passive"))
    )
    (net (code "128") (name "unconnected-(U16-I2S_TXD$35-Pad35)") (class "Default")
      (node (ref "U16") (pin "35") (pinfunction "I2S_TXD$35_35") (pintype "power_in"))
    )
    (net (code "129") (name "unconnected-(U16-I2S_WA$34-Pad34)") (class "Default")
      (node (ref "U16") (pin "34") (pinfunction "I2S_WA$34_34") (pintype "power_in"))
    )
    (net (code "130") (name "unconnected-(U16-RI$7-Pad7)") (class "Default")
      (node (ref "U16") (pin "7") (pinfunction "RI$7_7") (pintype "passive"))
    )
    (net (code "131") (name "unconnected-(U16-RSVD$2-Pad2)") (class "Default")
      (node (ref "U16") (pin "2") (pinfunction "RSVD$2_2") (pintype "passive"))
    )
    (net (code "132") (name "unconnected-(U16-RSVD$31-Pad31)") (class "Default")
      (node (ref "U16") (pin "31") (pinfunction "RSVD$31_31") (pintype "power_in"))
    )
    (net (code "133") (name "unconnected-(U16-SCL$27-Pad27)") (class "Default")
      (node (ref "U16") (pin "27") (pinfunction "SCL$27_27") (pintype "power_in"))
    )
    (net (code "134") (name "unconnected-(U16-SDA$26-Pad26)") (class "Default")
      (node (ref "U16") (pin "26") (pinfunction "SDA$26_26") (pintype "power_in"))
    )
    (net (code "135") (name "unconnected-(U16-SDIO_CLK$45-Pad45)") (class "Default")
      (node (ref "U16") (pin "45") (pinfunction "SDIO_CLK$45_45") (pintype "passive"))
    )
    (net (code "136") (name "unconnected-(U16-SDIO_CMD$46-Pad46)") (class "Default")
      (node (ref "U16") (pin "46") (pinfunction "SDIO_CMD$46_46") (pintype "bidirectional"))
    )
    (net (code "137") (name "unconnected-(U16-SDIO_D0$47-Pad47)") (class "Default")
      (node (ref "U16") (pin "47") (pinfunction "SDIO_D0$47_47") (pintype "bidirectional"))
    )
    (net (code "138") (name "unconnected-(U16-SDIO_D1$49-Pad49)") (class "Default")
      (node (ref "U16") (pin "49") (pinfunction "SDIO_D1$49_49") (pintype "bidirectional"))
    )
    (net (code "139") (name "unconnected-(U16-SDIO_D2$44-Pad44)") (class "Default")
      (node (ref "U16") (pin "44") (pinfunction "SDIO_D2$44_44") (pintype "bidirectional"))
    )
    (net (code "140") (name "unconnected-(U16-SDIO_D3$48-Pad48)") (class "Default")
      (node (ref "U16") (pin "48") (pinfunction "SDIO_D3$48_48") (pintype "bidirectional"))
    )
    (net (code "141") (name "unconnected-(U16-V_USB_DET$17-Pad17)") (class "Default")
      (node (ref "U16") (pin "17") (pinfunction "V_USB_DET$17_17") (pintype "passive"))
    )
    (net (code "142") (name "unconnected-(U19-ALT-Pad5)") (class "Default")
      (node (ref "U19") (pin "5") (pinfunction "ALT_5") (pintype "passive"))
    )
  )
)
